# Sheet1.net
KiCad netlist of a schematic drawn in Altium Designer
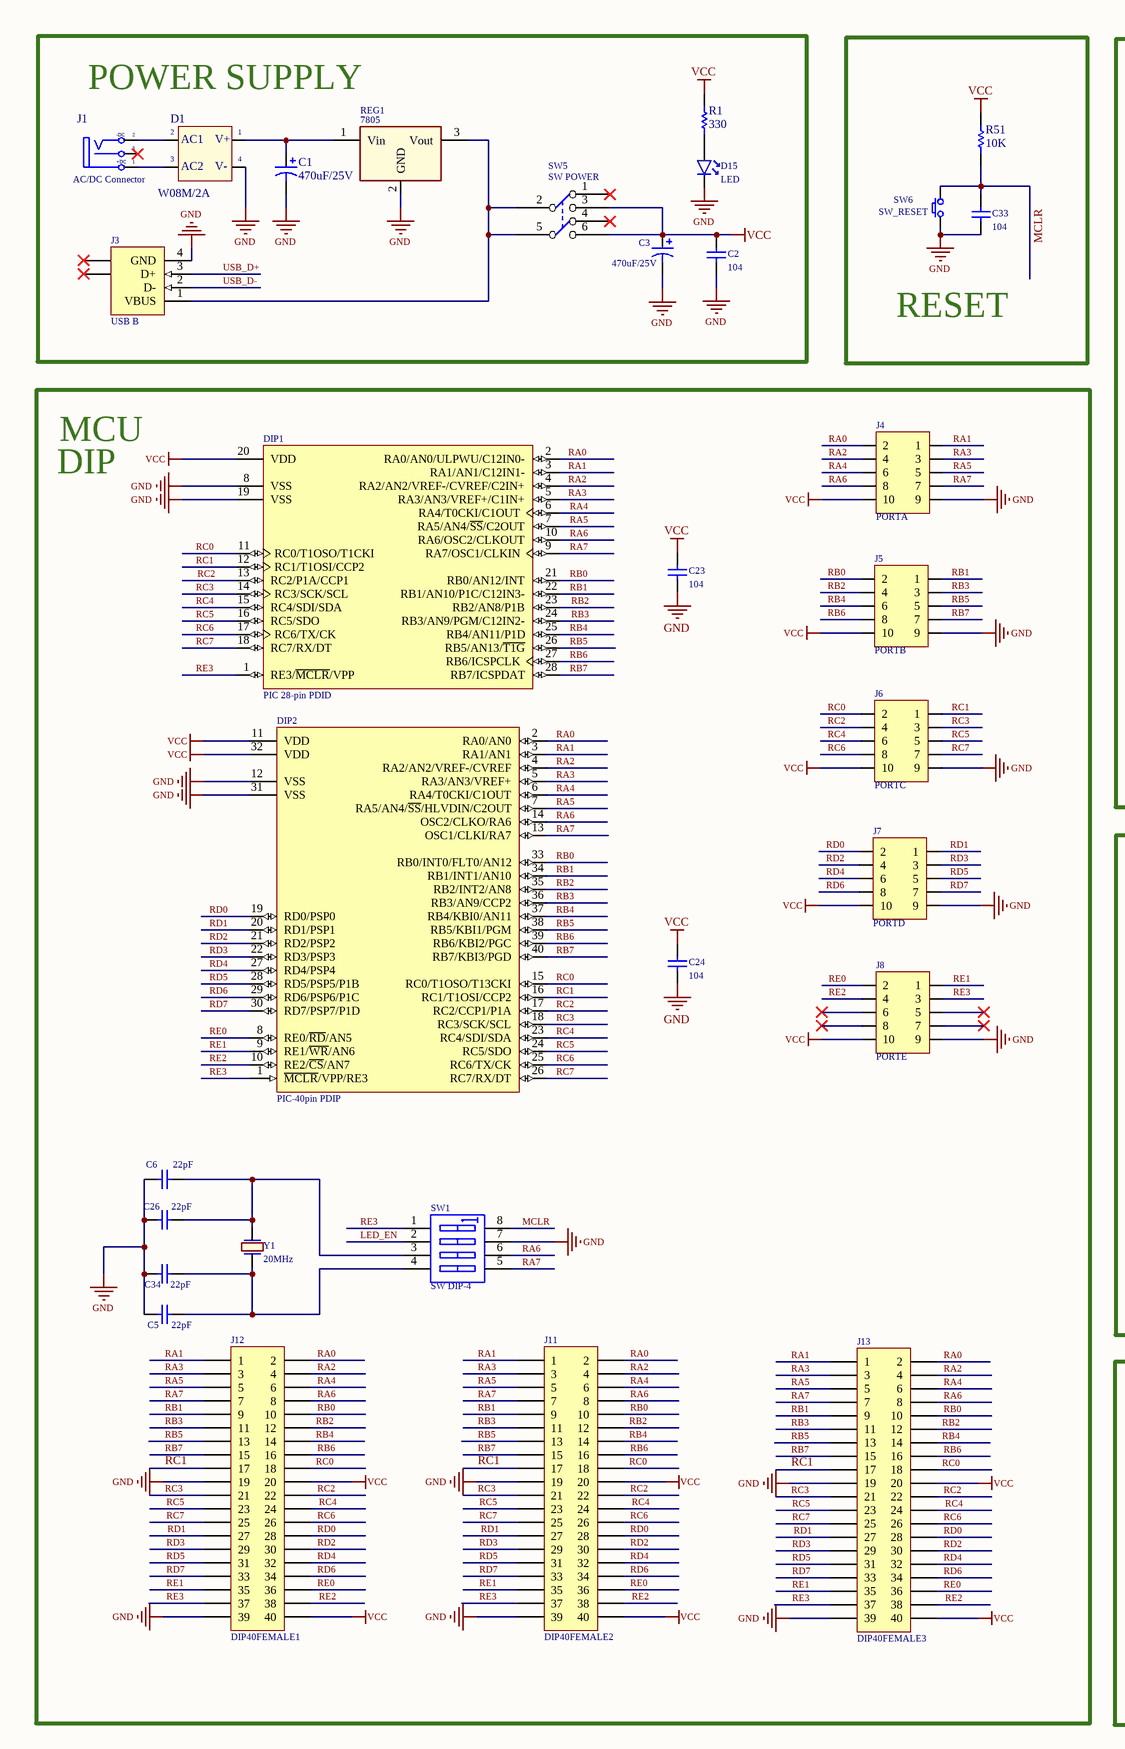
[diagram p0: Sheet1.SchDoc, left]
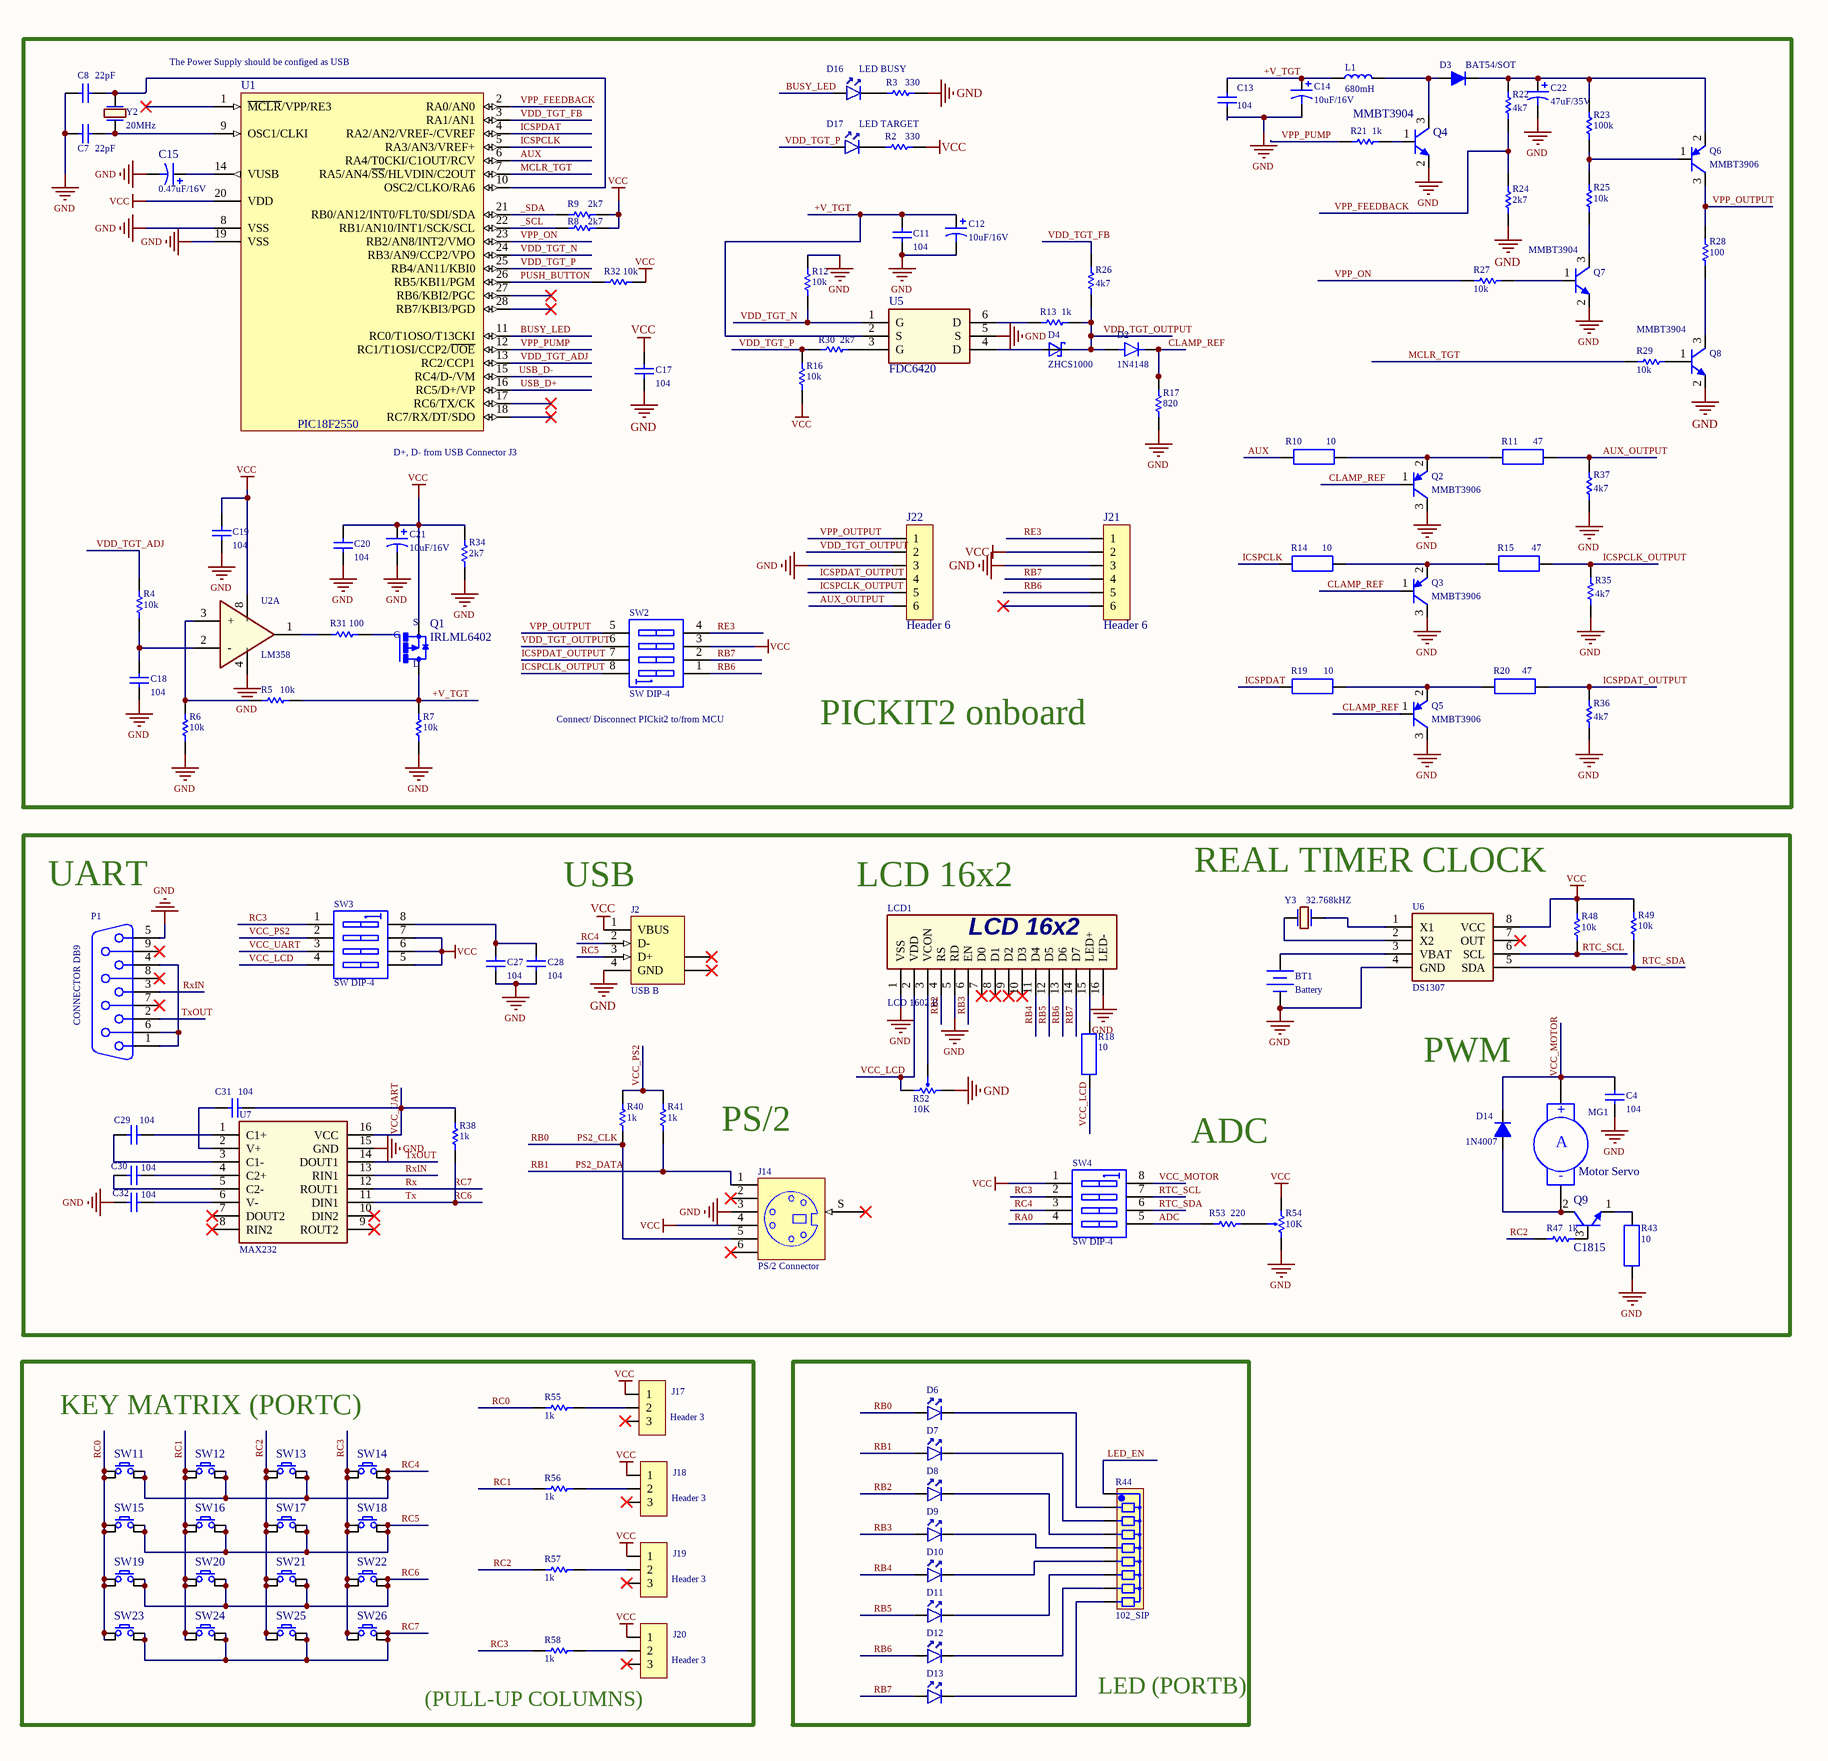
[diagram p1: Sheet1.SchDoc, right]

(export (version "E")
  (design (tool "Eeschema 10.0.6"))
  (components
    (comp (ref "BT1")
      (value "Battery")
      (footprint "CON CR2032")
      (libsource (lib "BKIT4U_LIB") (part "Battery"))
    )
    (comp (ref "C1")
      (value "470uF/25V")
      (footprint "CYL/D.300/LS.150/.031")
      (description "Polarized Capacitor (Axial)")
      (fields (field (name "PUBLISHER") "Altium Limited"))
      (libsource (lib "My Library") (part "Cap Pol 8mm"))
    )
    (comp (ref "C2")
      (value "104")
      (footprint "C 104")
      (description "Capacitor non-pol")
      (libsource (lib "BKIT4U_LIB") (part "Capacitor NP"))
    )
    (comp (ref "C3")
      (value "470uF/25V")
      (footprint "CYL/D.300/LS.150/.031")
      (description "Polarized Capacitor (Axial)")
      (fields (field (name "PUBLISHER") "Altium Limited"))
      (libsource (lib "My Library") (part "Cap Pol 8mm"))
    )
    (comp (ref "C4")
      (value "104")
      (footprint "C 0805 (2012)")
      (description "Capacitor non-pol")
      (libsource (lib "BKIT4U_LIB") (part "Capacitor NP"))
    )
    (comp (ref "C5")
      (value "22pF")
      (footprint "C 0805 (2012)")
      (description "Capacitor non-pol")
      (libsource (lib "BKIT4U_LIB") (part "Capacitor NP"))
    )
    (comp (ref "C6")
      (value "22pF")
      (footprint "C 0805 (2012)")
      (description "Capacitor non-pol")
      (libsource (lib "BKIT4U_LIB") (part "Capacitor NP"))
    )
    (comp (ref "C7")
      (value "22pF")
      (footprint "C 0805 (2012)")
      (description "Capacitor non-pol")
      (libsource (lib "BKIT4U_LIB") (part "Capacitor NP"))
    )
    (comp (ref "C8")
      (value "22pF")
      (footprint "C 0805 (2012)")
      (description "Capacitor non-pol")
      (libsource (lib "BKIT4U_LIB") (part "Capacitor NP"))
    )
    (comp (ref "C11")
      (value "104")
      (footprint "C 0805 (2012)")
      (description "Capacitor non-pol")
      (libsource (lib "BKIT4U_LIB") (part "Capacitor NP"))
    )
    (comp (ref "C12")
      (value "10uF/16V")
      (footprint "C5mm")
      (description "Polarized Capacitor (Axial)")
      (fields (field (name "PUBLISHER") "Altium Limited"))
      (libsource (lib "My Library") (part "Cap Pol 5mm"))
    )
    (comp (ref "C13")
      (value "104")
      (footprint "C 0805 (2012)")
      (description "Capacitor non-pol")
      (libsource (lib "BKIT4U_LIB") (part "Capacitor NP"))
    )
    (comp (ref "C14")
      (value "10uF/16V")
      (footprint "C5mm")
      (description "Polarized Capacitor (Axial)")
      (fields (field (name "PUBLISHER") "Altium Limited"))
      (libsource (lib "My Library") (part "Cap Pol 5mm"))
    )
    (comp (ref "C15")
      (value "0.47uF/16V")
      (footprint "C5mm")
      (description "Polarized Capacitor (Axial)")
      (fields (field (name "PUBLISHER") "Altium Limited"))
      (libsource (lib "My Library") (part "Cap Pol 5mm"))
    )
    (comp (ref "C17")
      (value "104")
      (footprint "C 0805 (2012)")
      (description "Capacitor non-pol")
      (libsource (lib "BKIT4U_LIB") (part "Capacitor NP"))
    )
    (comp (ref "C18")
      (value "104")
      (footprint "C 0805 (2012)")
      (description "Capacitor non-pol")
      (libsource (lib "BKIT4U_LIB") (part "Capacitor NP"))
    )
    (comp (ref "C19")
      (value "104")
      (footprint "C 0805 (2012)")
      (description "Capacitor non-pol")
      (libsource (lib "BKIT4U_LIB") (part "Capacitor NP"))
    )
    (comp (ref "C20")
      (value "104")
      (footprint "C 0805 (2012)")
      (description "Capacitor non-pol")
      (libsource (lib "BKIT4U_LIB") (part "Capacitor NP"))
    )
    (comp (ref "C21")
      (value "10uF/16V")
      (footprint "C5mm")
      (description "Polarized Capacitor (Axial)")
      (fields (field (name "PUBLISHER") "Altium Limited"))
      (libsource (lib "My Library") (part "Cap Pol 5mm"))
    )
    (comp (ref "C22")
      (value "47uF/35V")
      (footprint "C5mm")
      (description "Polarized Capacitor (Axial)")
      (fields (field (name "PUBLISHER") "Altium Limited"))
      (libsource (lib "My Library") (part "Cap Pol 5mm"))
    )
    (comp (ref "C23")
      (value "104")
      (footprint "C 0805 (2012)")
      (description "Capacitor non-pol")
      (libsource (lib "BKIT4U_LIB") (part "Capacitor NP"))
    )
    (comp (ref "C24")
      (value "104")
      (footprint "C 0805 (2012)")
      (description "Capacitor non-pol")
      (libsource (lib "BKIT4U_LIB") (part "Capacitor NP"))
    )
    (comp (ref "C26")
      (value "22pF")
      (footprint "C 0805 (2012)")
      (description "Capacitor non-pol")
      (libsource (lib "BKIT4U_LIB") (part "Capacitor NP"))
    )
    (comp (ref "C27")
      (value "104")
      (footprint "C 0805 (2012)")
      (description "Capacitor non-pol")
      (libsource (lib "BKIT4U_LIB") (part "Capacitor NP"))
    )
    (comp (ref "C28")
      (value "104")
      (footprint "C 0805 (2012)")
      (description "Capacitor non-pol")
      (libsource (lib "BKIT4U_LIB") (part "Capacitor NP"))
    )
    (comp (ref "C29")
      (value "104")
      (footprint "C 0805 (2012)")
      (description "Capacitor non-pol")
      (libsource (lib "BKIT4U_LIB") (part "Capacitor NP"))
    )
    (comp (ref "C30")
      (value "104")
      (footprint "C 0805 (2012)")
      (description "Capacitor non-pol")
      (libsource (lib "BKIT4U_LIB") (part "Capacitor NP"))
    )
    (comp (ref "C31")
      (value "104")
      (footprint "C 0805 (2012)")
      (description "Capacitor non-pol")
      (libsource (lib "BKIT4U_LIB") (part "Capacitor NP"))
    )
    (comp (ref "C32")
      (value "104")
      (footprint "C 0805 (2012)")
      (description "Capacitor non-pol")
      (libsource (lib "BKIT4U_LIB") (part "Capacitor NP"))
    )
    (comp (ref "C33")
      (value "104")
      (footprint "C 0805 (2012)")
      (description "Capacitor non-pol")
      (libsource (lib "BKIT4U_LIB") (part "Capacitor NP"))
    )
    (comp (ref "C34")
      (value "22pF")
      (footprint "C 0805 (2012)")
      (description "Capacitor non-pol")
      (libsource (lib "BKIT4U_LIB") (part "Capacitor NP"))
    )
    (comp (ref "D1")
      (value "W08M/2A")
      (footprint "BRIDGE DIODE 2A")
      (description "Convert AC to DC voltage, 4 pin")
      (libsource (lib "BKIT4U_LIB") (part "Diode Bridge"))
    )
    (comp (ref "D2")
      (value "1N4148")
      (footprint "SOT-23")
      (description "DIODE FAST SIGNAL 500MA/100V")
      (fields (field (name "MF") "MICROSS/On Semiconductor"))
      (libsource (lib "1N4148") (part "1N4148"))
    )
    (comp (ref "D3")
      (value "BAT54/SOT")
      (footprint "SOT-23")
      (description "Default Diode")
      (fields (field (name "PUBLISHER") "Altium Limited"))
      (libsource (lib "BKIT4U_LIB") (part "Diode"))
    )
    (comp (ref "D4")
      (value "ZHCS1000")
      (footprint "SOT-23")
      (description "Diode Schottky 40V 1A _DC_ Surface Mount SOT-23-3")
      (fields (field (name "MF") "Diodes Inc."))
      (libsource (lib "ZHCS1000") (part "ZHCS1000"))
    )
    (comp (ref "D6")
      (value "IR LED")
      (footprint "LED 3MM")
      (description "IR Led")
      (fields (field (name "PUBLISHER") "Altium Limited"))
      (libsource (lib "BKIT4U_LIB") (part "IR Led"))
    )
    (comp (ref "D7")
      (value "IR LED")
      (footprint "LED 3MM")
      (description "IR Led")
      (fields (field (name "PUBLISHER") "Altium Limited"))
      (libsource (lib "BKIT4U_LIB") (part "IR Led"))
    )
    (comp (ref "D8")
      (value "IR LED")
      (footprint "LED 3MM")
      (description "IR Led")
      (fields (field (name "PUBLISHER") "Altium Limited"))
      (libsource (lib "BKIT4U_LIB") (part "IR Led"))
    )
    (comp (ref "D9")
      (value "IR LED")
      (footprint "LED 3MM")
      (description "IR Led")
      (fields (field (name "PUBLISHER") "Altium Limited"))
      (libsource (lib "BKIT4U_LIB") (part "IR Led"))
    )
    (comp (ref "D10")
      (value "IR LED")
      (footprint "LED 3MM")
      (description "IR Led")
      (fields (field (name "PUBLISHER") "Altium Limited"))
      (libsource (lib "BKIT4U_LIB") (part "IR Led"))
    )
    (comp (ref "D11")
      (value "IR LED")
      (footprint "LED 3MM")
      (description "IR Led")
      (fields (field (name "PUBLISHER") "Altium Limited"))
      (libsource (lib "BKIT4U_LIB") (part "IR Led"))
    )
    (comp (ref "D12")
      (value "IR LED")
      (footprint "LED 3MM")
      (description "IR Led")
      (fields (field (name "PUBLISHER") "Altium Limited"))
      (libsource (lib "BKIT4U_LIB") (part "IR Led"))
    )
    (comp (ref "D13")
      (value "IR LED")
      (footprint "LED 3MM")
      (description "IR Led")
      (fields (field (name "PUBLISHER") "Altium Limited"))
      (libsource (lib "BKIT4U_LIB") (part "IR Led"))
    )
    (comp (ref "D14")
      (value "1N4007")
      (footprint "D1A")
      (description "Diode 1A")
      (libsource (lib "My Library") (part "D1A"))
    )
    (comp (ref "D15")
      (value "LED")
      (footprint "LED 3MM")
      (description "IR Led")
      (fields (field (name "PUBLISHER") "Altium Limited"))
      (libsource (lib "BKIT4U_LIB") (part "IR Led"))
    )
    (comp (ref "D16")
      (value "LED BUSY")
      (footprint "LED 3MM")
      (description "IR Led")
      (fields (field (name "PUBLISHER") "Altium Limited"))
      (libsource (lib "BKIT4U_LIB") (part "IR Led"))
    )
    (comp (ref "D17")
      (value "LED TARGET")
      (footprint "LED 3MM")
      (description "IR Led")
      (fields (field (name "PUBLISHER") "Altium Limited"))
      (libsource (lib "BKIT4U_LIB") (part "IR Led"))
    )
    (comp (ref "DIP1")
      (value "PIC 28-pin PDID")
      (footprint "SPDIP300-SP28")
      (fields (field (name "PUBLISHER") "Altium Limited"))
      (libsource (lib "Microchip Microcontroller 8-Bit PIC16") (part "PIC16F886-I/SP"))
    )
    (comp (ref "DIP2")
      (value "PIC-40pin PDIP")
      (footprint "PDIP600-P40")
      (fields (field (name "PUBLISHER") "Altium Limited"))
      (libsource (lib "Microchip Microcontroller 8-Bit PIC18") (part "PIC18F4620-I/P"))
    )
    (comp (ref "J1")
      (value "AC/DC Connector")
      (footprint "CON PWR 5MM")
      (description "DC input connector")
      (libsource (lib "BKIT4U_LIB") (part "CON DC PWR"))
    )
    (comp (ref "J2")
      (value "USB B")
      (footprint "CON USB B")
      (description "USB type B, 4 pins")
      (libsource (lib "BKIT4U_LIB") (part "CON USB B"))
    )
    (comp (ref "J3")
      (value "USB B")
      (footprint "CON USB B")
      (description "USB type B, 4 pins")
      (libsource (lib "") (part "CON USB B_1"))
    )
    (comp (ref "J4")
      (value "PORTA")
      (footprint "Header 5x2")
      (description "Header, 5-Pin, Dual row")
      (fields (field (name "PUBLISHER") "Altium Limited"))
      (libsource (lib "BKIT4U_LIB") (part "Header 5X2"))
    )
    (comp (ref "J5")
      (value "PORTB")
      (footprint "Header 5x2")
      (description "Header, 5-Pin, Dual row")
      (fields (field (name "PUBLISHER") "Altium Limited"))
      (libsource (lib "BKIT4U_LIB") (part "Header 5X2"))
    )
    (comp (ref "J6")
      (value "PORTC")
      (footprint "Header 5x2")
      (description "Header, 5-Pin, Dual row")
      (fields (field (name "PUBLISHER") "Altium Limited"))
      (libsource (lib "BKIT4U_LIB") (part "Header 5X2"))
    )
    (comp (ref "J7")
      (value "PORTD")
      (footprint "Header 5x2")
      (description "Header, 5-Pin, Dual row")
      (fields (field (name "PUBLISHER") "Altium Limited"))
      (libsource (lib "BKIT4U_LIB") (part "Header 5X2"))
    )
    (comp (ref "J8")
      (value "PORTE")
      (footprint "Header 5x2")
      (description "Header, 5-Pin, Dual row")
      (fields (field (name "PUBLISHER") "Altium Limited"))
      (libsource (lib "BKIT4U_LIB") (part "Header 5X2"))
    )
    (comp (ref "J11")
      (value "DIP40FEMALE2")
      (footprint "HDR2X20")
      (description "Header, 20-Pin, Dual row")
      (fields (field (name "PUBLISHER") "Altium Limited"))
      (libsource (lib "My library altium") (part "Header 20X2"))
    )
    (comp (ref "J12")
      (value "DIP40FEMALE1")
      (footprint "HDR2X20")
      (description "Header, 20-Pin, Dual row")
      (fields (field (name "PUBLISHER") "Altium Limited"))
      (libsource (lib "My library altium") (part "Header 20X2"))
    )
    (comp (ref "J13")
      (value "DIP40FEMALE3")
      (footprint "HDR2X20")
      (description "Header, 20-Pin, Dual row")
      (fields (field (name "PUBLISHER") "Altium Limited"))
      (libsource (lib "My library altium") (part "Header 20X2"))
    )
    (comp (ref "J14")
      (value "PS/2 Connector")
      (footprint "PS2-6PIN")
      (description "6 Pin Through Hole PS2 Socket (Kycon P/N)")
      (fields (field (name "PUBLISHER") "Altium Limited"))
      (libsource (lib "Miscellaneous Connectors") (part "PS2-6PIN"))
    )
    (comp (ref "J17")
      (value "Header 3")
      (footprint "Header 3")
      (description "Header, 3-Pin")
      (libsource (lib "BKIT4U_LIB") (part "Header 3"))
    )
    (comp (ref "J18")
      (value "Header 3")
      (footprint "Header 3")
      (description "Header, 3-Pin")
      (libsource (lib "BKIT4U_LIB") (part "Header 3"))
    )
    (comp (ref "J19")
      (value "Header 3")
      (footprint "Header 3")
      (description "Header, 3-Pin")
      (libsource (lib "BKIT4U_LIB") (part "Header 3"))
    )
    (comp (ref "J20")
      (value "Header 3")
      (footprint "Header 3")
      (description "Header, 3-Pin")
      (libsource (lib "BKIT4U_LIB") (part "Header 3"))
    )
    (comp (ref "J21")
      (value "Header 6")
      (footprint "Header 6")
      (description "Header, 6-Pin")
      (libsource (lib "BKIT4U_LIB") (part "Header 6"))
    )
    (comp (ref "J22")
      (value "Header 6")
      (footprint "Header 6")
      (description "Header, 6-Pin")
      (libsource (lib "BKIT4U_LIB") (part "Header 6"))
    )
    (comp (ref "L1")
      (value "680mH")
      (footprint "R 1/2W")
      (description "Inductor")
      (libsource (lib "BKIT4U_LIB") (part "Inductor"))
    )
    (comp (ref "LCD1")
      (value "LCD 1602 B")
      (footprint "LCD 16x2")
      (description "Character LCD 16x2")
      (libsource (lib "BKIT4U_LIB") (part "LCD 16x2"))
    )
    (comp (ref "MG1")
      (value "Motor Servo")
      (footprint "R 1206 (3216)")
      (description "Servo Motor")
      (fields (field (name "PUBLISHER") "Altium Limited"))
      (libsource (lib "Miscellaneous Devices") (part "Motor Servo"))
    )
    (comp (ref "P1")
      (value "CONNECTOR DB9")
      (footprint "CON DB9 FEMALE ROTATY")
      (description "Connector D-Sub 9")
      (libsource (lib "BKIT4U_LIB") (part "CON DB-9"))
    )
    (comp (ref "Q1")
      (value "IRLML6402")
      (footprint "SOT23")
      (description "P-Channel 20V 3.7A _Ta_ 1.3W _Ta_ Surface Mount Micro3â„¢/SOT-23")
      (fields (field (name "MF") "Infineon Technologies"))
      (libsource (lib "IRLML6402") (part "IRLML6402"))
    )
    (comp (ref "Q2")
      (value "MMBT3906")
      (footprint "SOT-23")
      (description "PNP Bipolar Transistor")
      (fields (field (name "PUBLISHER") "Altium Limited"))
      (libsource (lib "BKIT4U_LIB") (part "Transistor PNP"))
    )
    (comp (ref "Q3")
      (value "MMBT3906")
      (footprint "SOT-23")
      (description "PNP Bipolar Transistor")
      (fields (field (name "PUBLISHER") "Altium Limited"))
      (libsource (lib "BKIT4U_LIB") (part "Transistor PNP"))
    )
    (comp (ref "Q4")
      (value "MMBT3904")
      (footprint "SOT-23")
      (description "NPN Bipolar Transistor")
      (libsource (lib "BKIT4U_LIB") (part "Transistor NPN"))
    )
    (comp (ref "Q5")
      (value "MMBT3906")
      (footprint "SOT-23")
      (description "PNP Bipolar Transistor")
      (fields (field (name "PUBLISHER") "Altium Limited"))
      (libsource (lib "BKIT4U_LIB") (part "Transistor PNP"))
    )
    (comp (ref "Q6")
      (value "MMBT3906")
      (footprint "SOT-23")
      (description "PNP Bipolar Transistor")
      (fields (field (name "PUBLISHER") "Altium Limited"))
      (libsource (lib "BKIT4U_LIB") (part "Transistor PNP"))
    )
    (comp (ref "Q7")
      (value "MMBT3904")
      (footprint "SOT-23")
      (description "NPN Bipolar Transistor")
      (libsource (lib "BKIT4U_LIB") (part "Transistor NPN"))
    )
    (comp (ref "Q8")
      (value "MMBT3904")
      (footprint "SOT-23")
      (description "NPN Bipolar Transistor")
      (libsource (lib "BKIT4U_LIB") (part "Transistor NPN"))
    )
    (comp (ref "Q9")
      (value "C1815")
      (footprint "TO-126")
      (description "NPN Bipolar Transistor")
      (libsource (lib "BKIT4U_LIB") (part "Transistor NPN - C1815"))
    )
    (comp (ref "R1")
      (value "330")
      (footprint "R 1/4W")
      (description "Resistor")
      (fields (field (name "PUBLISHER") "Altium Limited"))
      (libsource (lib "BKIT4U_LIB") (part "Resistor"))
    )
    (comp (ref "R2")
      (value "330")
      (footprint "R 1/4W")
      (description "Resistor")
      (fields (field (name "PUBLISHER") "Altium Limited"))
      (libsource (lib "BKIT4U_LIB") (part "Resistor"))
    )
    (comp (ref "R3")
      (value "330")
      (footprint "R 1/4W")
      (description "Resistor")
      (fields (field (name "PUBLISHER") "Altium Limited"))
      (libsource (lib "BKIT4U_LIB") (part "Resistor"))
    )
    (comp (ref "R4")
      (value "10k")
      (footprint "R 1/4W")
      (description "Resistor")
      (fields (field (name "PUBLISHER") "Altium Limited"))
      (libsource (lib "BKIT4U_LIB") (part "Resistor"))
    )
    (comp (ref "R5")
      (value "10k")
      (footprint "R 1/4W")
      (description "Resistor")
      (fields (field (name "PUBLISHER") "Altium Limited"))
      (libsource (lib "BKIT4U_LIB") (part "Resistor"))
    )
    (comp (ref "R6")
      (value "10k")
      (footprint "R 1/4W")
      (description "Resistor")
      (fields (field (name "PUBLISHER") "Altium Limited"))
      (libsource (lib "BKIT4U_LIB") (part "Resistor"))
    )
    (comp (ref "R7")
      (value "10k")
      (footprint "R 1/4W")
      (description "Resistor")
      (fields (field (name "PUBLISHER") "Altium Limited"))
      (libsource (lib "BKIT4U_LIB") (part "Resistor"))
    )
    (comp (ref "R8")
      (value "2k7")
      (footprint "R 1/4W")
      (description "Resistor")
      (fields (field (name "PUBLISHER") "Altium Limited"))
      (libsource (lib "BKIT4U_LIB") (part "Resistor"))
    )
    (comp (ref "R9")
      (value "2k7")
      (footprint "R 1/4W")
      (description "Resistor")
      (fields (field (name "PUBLISHER") "Altium Limited"))
      (libsource (lib "BKIT4U_LIB") (part "Resistor"))
    )
    (comp (ref "R10")
      (value "10")
      (footprint "R 1/4W")
      (description "Resistor 1W")
      (libsource (lib "My Library") (part "R1W"))
    )
    (comp (ref "R11")
      (value "47")
      (footprint "R 1/4W")
      (description "Resistor 1W")
      (libsource (lib "My Library") (part "R1W"))
    )
    (comp (ref "R12")
      (value "10k")
      (footprint "R 1/4W")
      (description "Resistor")
      (fields (field (name "PUBLISHER") "Altium Limited"))
      (libsource (lib "BKIT4U_LIB") (part "Resistor"))
    )
    (comp (ref "R13")
      (value "1k")
      (footprint "R 1/4W")
      (description "Resistor")
      (fields (field (name "PUBLISHER") "Altium Limited"))
      (libsource (lib "BKIT4U_LIB") (part "Resistor"))
    )
    (comp (ref "R14")
      (value "10")
      (footprint "R 1/4W")
      (description "Resistor 1W")
      (libsource (lib "My Library") (part "R1W"))
    )
    (comp (ref "R15")
      (value "47")
      (footprint "R 1/4W")
      (description "Resistor 1W")
      (libsource (lib "My Library") (part "R1W"))
    )
    (comp (ref "R16")
      (value "10k")
      (footprint "R 1/4W")
      (description "Resistor")
      (fields (field (name "PUBLISHER") "Altium Limited"))
      (libsource (lib "BKIT4U_LIB") (part "Resistor"))
    )
    (comp (ref "R17")
      (value "820")
      (footprint "R 1/4W")
      (description "Resistor")
      (fields (field (name "PUBLISHER") "Altium Limited"))
      (libsource (lib "BKIT4U_LIB") (part "Resistor"))
    )
    (comp (ref "R18")
      (value "10")
      (footprint "R 1/4W")
      (description "Resistor 1W")
      (libsource (lib "My Library") (part "R1W"))
    )
    (comp (ref "R19")
      (value "10")
      (footprint "R 1/4W")
      (description "Resistor 1W")
      (libsource (lib "My Library") (part "R1W"))
    )
    (comp (ref "R20")
      (value "47")
      (footprint "R 1/4W")
      (description "Resistor 1W")
      (libsource (lib "My Library") (part "R1W"))
    )
    (comp (ref "R21")
      (value "1k")
      (footprint "R 1/4W")
      (description "Resistor")
      (fields (field (name "PUBLISHER") "Altium Limited"))
      (libsource (lib "BKIT4U_LIB") (part "Resistor"))
    )
    (comp (ref "R22")
      (value "4k7")
      (footprint "R 1/4W")
      (description "Resistor")
      (fields (field (name "PUBLISHER") "Altium Limited"))
      (libsource (lib "BKIT4U_LIB") (part "Resistor"))
    )
    (comp (ref "R23")
      (value "100k")
      (footprint "R 1/4W")
      (description "Resistor")
      (fields (field (name "PUBLISHER") "Altium Limited"))
      (libsource (lib "BKIT4U_LIB") (part "Resistor"))
    )
    (comp (ref "R24")
      (value "2k7")
      (footprint "R 1/4W")
      (description "Resistor")
      (fields (field (name "PUBLISHER") "Altium Limited"))
      (libsource (lib "BKIT4U_LIB") (part "Resistor"))
    )
    (comp (ref "R25")
      (value "10k")
      (footprint "R 1/4W")
      (description "Resistor")
      (fields (field (name "PUBLISHER") "Altium Limited"))
      (libsource (lib "BKIT4U_LIB") (part "Resistor"))
    )
    (comp (ref "R26")
      (value "4k7")
      (footprint "R 1/4W")
      (description "Resistor")
      (fields (field (name "PUBLISHER") "Altium Limited"))
      (libsource (lib "BKIT4U_LIB") (part "Resistor"))
    )
    (comp (ref "R27")
      (value "10k")
      (footprint "R 1/4W")
      (description "Resistor")
      (fields (field (name "PUBLISHER") "Altium Limited"))
      (libsource (lib "BKIT4U_LIB") (part "Resistor"))
    )
    (comp (ref "R28")
      (value "100")
      (footprint "R 1/4W")
      (description "Resistor")
      (fields (field (name "PUBLISHER") "Altium Limited"))
      (libsource (lib "BKIT4U_LIB") (part "Resistor"))
    )
    (comp (ref "R29")
      (value "10k")
      (footprint "R 1/4W")
      (description "Resistor")
      (fields (field (name "PUBLISHER") "Altium Limited"))
      (libsource (lib "BKIT4U_LIB") (part "Resistor"))
    )
    (comp (ref "R30")
      (value "2k7")
      (footprint "R 1/4W")
      (description "Resistor")
      (fields (field (name "PUBLISHER") "Altium Limited"))
      (libsource (lib "BKIT4U_LIB") (part "Resistor"))
    )
    (comp (ref "R31")
      (value "100")
      (footprint "R 1/4W")
      (description "Resistor")
      (fields (field (name "PUBLISHER") "Altium Limited"))
      (libsource (lib "BKIT4U_LIB") (part "Resistor"))
    )
    (comp (ref "R32")
      (value "10k")
      (footprint "R 1/4W")
      (description "Resistor")
      (fields (field (name "PUBLISHER") "Altium Limited"))
      (libsource (lib "BKIT4U_LIB") (part "Resistor"))
    )
    (comp (ref "R34")
      (value "2k7")
      (footprint "R 1/4W")
      (description "Resistor")
      (fields (field (name "PUBLISHER") "Altium Limited"))
      (libsource (lib "BKIT4U_LIB") (part "Resistor"))
    )
    (comp (ref "R35")
      (value "4k7")
      (footprint "R 1/4W")
      (description "Resistor")
      (fields (field (name "PUBLISHER") "Altium Limited"))
      (libsource (lib "BKIT4U_LIB") (part "Resistor"))
    )
    (comp (ref "R36")
      (value "4k7")
      (footprint "R 1/4W")
      (description "Resistor")
      (fields (field (name "PUBLISHER") "Altium Limited"))
      (libsource (lib "BKIT4U_LIB") (part "Resistor"))
    )
    (comp (ref "R37")
      (value "4k7")
      (footprint "R 1/4W")
      (description "Resistor")
      (fields (field (name "PUBLISHER") "Altium Limited"))
      (libsource (lib "BKIT4U_LIB") (part "Resistor"))
    )
    (comp (ref "R38")
      (value "1k")
      (footprint "R 1/4W")
      (description "Resistor")
      (fields (field (name "PUBLISHER") "Altium Limited"))
      (libsource (lib "BKIT4U_LIB") (part "Resistor"))
    )
    (comp (ref "R40")
      (value "1k")
      (footprint "R 1/4W")
      (description "Resistor")
      (fields (field (name "PUBLISHER") "Altium Limited"))
      (libsource (lib "BKIT4U_LIB") (part "Resistor"))
    )
    (comp (ref "R41")
      (value "1k")
      (footprint "R 1/4W")
      (description "Resistor")
      (fields (field (name "PUBLISHER") "Altium Limited"))
      (libsource (lib "BKIT4U_LIB") (part "Resistor"))
    )
    (comp (ref "R43")
      (value "10")
      (footprint "R 1/4W")
      (description "Resistor 1W")
      (libsource (lib "My Library") (part "R1W"))
    )
    (comp (ref "R44")
      (value "102_SIP")
      (footprint "RN8")
      (description "Resistor 8 (Thanh)")
      (libsource (lib "My Library") (part "RN8"))
    )
    (comp (ref "R47")
      (value "1k")
      (footprint "R 1/4W")
      (description "Resistor")
      (fields (field (name "PUBLISHER") "Altium Limited"))
      (libsource (lib "BKIT4U_LIB") (part "Resistor"))
    )
    (comp (ref "R48")
      (value "10k")
      (footprint "R 1/4W")
      (description "Resistor")
      (fields (field (name "PUBLISHER") "Altium Limited"))
      (libsource (lib "BKIT4U_LIB") (part "Resistor"))
    )
    (comp (ref "R49")
      (value "10k")
      (footprint "R 1/4W")
      (description "Resistor")
      (fields (field (name "PUBLISHER") "Altium Limited"))
      (libsource (lib "BKIT4U_LIB") (part "Resistor"))
    )
    (comp (ref "R51")
      (value "10K")
      (footprint "R 1/4W")
      (description "Resistor")
      (fields (field (name "PUBLISHER") "Altium Limited"))
      (libsource (lib "BKIT4U_LIB") (part "Resistor"))
    )
    (comp (ref "R52")
      (value "10K")
      (footprint "R VAR D")
      (description "Resistor Variable")
      (libsource (lib "BKIT4U_LIB") (part "Resistor Variable"))
    )
    (comp (ref "R53")
      (value "220")
      (footprint "R 1/4W")
      (description "Resistor")
      (fields (field (name "PUBLISHER") "Altium Limited"))
      (libsource (lib "BKIT4U_LIB") (part "Resistor"))
    )
    (comp (ref "R54")
      (value "10K")
      (footprint "R VAR B")
      (description "Resistor Variable")
      (libsource (lib "BKIT4U_LIB") (part "Resistor Variable"))
    )
    (comp (ref "R55")
      (value "1k")
      (footprint "R 1/4W")
      (description "Resistor")
      (fields (field (name "PUBLISHER") "Altium Limited"))
      (libsource (lib "BKIT4U_LIB") (part "Resistor"))
    )
    (comp (ref "R56")
      (value "1k")
      (footprint "R 1/4W")
      (description "Resistor")
      (fields (field (name "PUBLISHER") "Altium Limited"))
      (libsource (lib "BKIT4U_LIB") (part "Resistor"))
    )
    (comp (ref "R57")
      (value "1k")
      (footprint "R 1/4W")
      (description "Resistor")
      (fields (field (name "PUBLISHER") "Altium Limited"))
      (libsource (lib "BKIT4U_LIB") (part "Resistor"))
    )
    (comp (ref "R58")
      (value "1k")
      (footprint "R 1/4W")
      (description "Resistor")
      (fields (field (name "PUBLISHER") "Altium Limited"))
      (libsource (lib "BKIT4U_LIB") (part "Resistor"))
    )
    (comp (ref "REG1")
      (value "7805")
      (footprint "TO-220/HeatSink")
      (description "LDO Fixed Voltage regulator")
      (libsource (lib "BKIT4U_LIB") (part "78xx/78Mxx"))
    )
    (comp (ref "SW1")
      (value "SW DIP-4")
      (footprint "SW/DIP4")
      (description "WS-DITV 2.54 mm small compact THT flat actuator with top tape")
      (fields
        (field (name "MANUFACTURER") "Wurth Elektronik")
        (field (name "PART NO.") "418127160904")
        (field (name "CREATED BY") "Baojun Chen")
      )
      (libsource (lib "") (part "SWDIP4_1"))
    )
    (comp (ref "SW2")
      (value "SW DIP-4")
      (footprint "SW/DIP4")
      (description "WS-DITV 2.54 mm small compact THT flat actuator with top tape")
      (fields
        (field (name "MANUFACTURER") "Wurth Elektronik")
        (field (name "PART NO.") "418127160904")
        (field (name "CREATED BY") "Baojun Chen")
      )
      (libsource (lib "My Library") (part "SWDIP4"))
    )
    (comp (ref "SW3")
      (value "SW DIP-4")
      (footprint "SW/DIP4")
      (description "WS-DITV 2.54 mm small compact THT flat actuator with top tape")
      (fields
        (field (name "MANUFACTURER") "Wurth Elektronik")
        (field (name "PART NO.") "418127160904")
        (field (name "CREATED BY") "Baojun Chen")
      )
      (libsource (lib "") (part "SWDIP4_1"))
    )
    (comp (ref "SW4")
      (value "SW DIP-4")
      (footprint "SW/DIP4")
      (description "WS-DITV 2.54 mm small compact THT flat actuator with top tape")
      (fields
        (field (name "MANUFACTURER") "Wurth Elektronik")
        (field (name "PART NO.") "418127160904")
        (field (name "CREATED BY") "Baojun Chen")
      )
      (libsource (lib "") (part "SWDIP4_1"))
    )
    (comp (ref "SW5")
      (value "SW POWER")
      (footprint "SW/6/DPDT/PUSH")
      (libsource (lib "BKIT4U_LIB") (part "SW DPDT/2S"))
    )
    (comp (ref "SW6")
      (value "SW_RESET")
      (footprint "SW/2/DIP")
      (description "Tact switch 2 pin")
      (libsource (lib "BKIT4U_LIB") (part "SW SPST"))
    )
    (comp (ref "SW11")
      (value "Tact Switch")
      (footprint "SW/4/SMD/SMALL")
      (description "Tact switch 4 pin")
      (libsource (lib "BKIT4U_LIB") (part "SW SPST-4"))
    )
    (comp (ref "SW12")
      (value "Tact Switch")
      (footprint "SW/4/SMD/SMALL")
      (description "Tact switch 4 pin")
      (libsource (lib "BKIT4U_LIB") (part "SW SPST-4"))
    )
    (comp (ref "SW13")
      (value "Tact Switch")
      (footprint "SW/4/SMD/SMALL")
      (description "Tact switch 4 pin")
      (libsource (lib "BKIT4U_LIB") (part "SW SPST-4"))
    )
    (comp (ref "SW14")
      (value "Tact Switch")
      (footprint "SW/4/SMD/SMALL")
      (description "Tact switch 4 pin")
      (libsource (lib "BKIT4U_LIB") (part "SW SPST-4"))
    )
    (comp (ref "SW15")
      (value "Tact Switch")
      (footprint "SW/4/SMD/SMALL")
      (description "Tact switch 4 pin")
      (libsource (lib "BKIT4U_LIB") (part "SW SPST-4"))
    )
    (comp (ref "SW16")
      (value "Tact Switch")
      (footprint "SW/4/SMD/SMALL")
      (description "Tact switch 4 pin")
      (libsource (lib "BKIT4U_LIB") (part "SW SPST-4"))
    )
    (comp (ref "SW17")
      (value "Tact Switch")
      (footprint "SW/4/SMD/SMALL")
      (description "Tact switch 4 pin")
      (libsource (lib "BKIT4U_LIB") (part "SW SPST-4"))
    )
    (comp (ref "SW18")
      (value "Tact Switch")
      (footprint "SW/4/SMD/SMALL")
      (description "Tact switch 4 pin")
      (libsource (lib "BKIT4U_LIB") (part "SW SPST-4"))
    )
    (comp (ref "SW19")
      (value "Tact Switch")
      (footprint "SW/4/SMD/SMALL")
      (description "Tact switch 4 pin")
      (libsource (lib "BKIT4U_LIB") (part "SW SPST-4"))
    )
    (comp (ref "SW20")
      (value "Tact Switch")
      (footprint "SW/4/SMD/SMALL")
      (description "Tact switch 4 pin")
      (libsource (lib "BKIT4U_LIB") (part "SW SPST-4"))
    )
    (comp (ref "SW21")
      (value "Tact Switch")
      (footprint "SW/4/SMD/SMALL")
      (description "Tact switch 4 pin")
      (libsource (lib "BKIT4U_LIB") (part "SW SPST-4"))
    )
    (comp (ref "SW22")
      (value "Tact Switch")
      (footprint "SW/4/SMD/SMALL")
      (description "Tact switch 4 pin")
      (libsource (lib "BKIT4U_LIB") (part "SW SPST-4"))
    )
    (comp (ref "SW23")
      (value "Tact Switch")
      (footprint "SW/4/SMD/SMALL")
      (description "Tact switch 4 pin")
      (libsource (lib "BKIT4U_LIB") (part "SW SPST-4"))
    )
    (comp (ref "SW24")
      (value "Tact Switch")
      (footprint "SW/4/SMD/SMALL")
      (description "Tact switch 4 pin")
      (libsource (lib "BKIT4U_LIB") (part "SW SPST-4"))
    )
    (comp (ref "SW25")
      (value "Tact Switch")
      (footprint "SW/4/SMD/SMALL")
      (description "Tact switch 4 pin")
      (libsource (lib "BKIT4U_LIB") (part "SW SPST-4"))
    )
    (comp (ref "SW26")
      (value "Tact Switch")
      (footprint "SW/4/SMD/SMALL")
      (description "Tact switch 4 pin")
      (libsource (lib "BKIT4U_LIB") (part "SW SPST-4"))
    )
    (comp (ref "U1")
      (value "PIC18F2550")
      (footprint "SPDIP300-SP28")
      (fields (field (name "PUBLISHER") "Altium Limited"))
      (libsource (lib "Microchip Microcontroller 8-Bit PIC18") (part "PIC18F2550-I/SP"))
    )
    (comp (ref "U2")
      (value "LM358")
      (footprint "SOIC-8")
      (description "Low Power Dual Operational Amplifiers")
      (libsource (lib "BKIT4U_LIB") (part "LM358"))
    )
    (comp (ref "U5")
      (value "FDC6420")
      (footprint "SOT-6")
      (description "20V N & P-Channel PowerTrenchÒ MOSFETs")
      (libsource (lib "BKIT4U_LIB") (part "FDC6420"))
    )
    (comp (ref "U6") (value "DS1307") (footprint "DIP 8") (libsource (lib "BKIT4U_LIB") (part "DS1307")))
    (comp (ref "U7")
      (value "MAX232")
      (footprint "SOIC-16")
      (description "RS-232 Line Driver/Receiver")
      (libsource (lib "BKIT4U_LIB") (part "MAX232"))
    )
    (comp (ref "Y1")
      (value "20MHz")
      (footprint "Crystal HC49S DIP")
      (libsource (lib "BKIT4U_LIB") (part "Crystal"))
    )
    (comp (ref "Y2")
      (value "20MHz")
      (footprint "Crystal HC49S DIP")
      (libsource (lib "BKIT4U_LIB") (part "Crystal"))
    )
    (comp (ref "Y3") (value "32.768kHZ") (footprint "Crystal DIP-2") (libsource (lib "") (part "Crystal_1")))
  )
  (nets
    (net (code "1") (name "/+V_TGT") (class "Default")
      (node (ref "C11") (pin "1") (pinfunction "1_1") (pintype "passive"))
      (node (ref "C12") (pin "1") (pinfunction "1_1") (pintype "passive"))
      (node (ref "C13") (pin "1") (pinfunction "1_1") (pintype "passive"))
      (node (ref "C14") (pin "1") (pinfunction "1_1") (pintype "passive"))
      (node (ref "L1") (pin "1") (pinfunction "1_1") (pintype "passive"))
      (node (ref "Q1") (pin "3") (pinfunction "D_3") (pintype "passive"))
      (node (ref "R5") (pin "2") (pinfunction "2_2") (pintype "passive"))
      (node (ref "R7") (pin "2") (pinfunction "2_2") (pintype "passive"))
      (node (ref "U5") (pin "2") (pinfunction "S_2") (pintype "passive"))
    )
    (net (code "2") (name "/ADC") (class "Default")
      (node (ref "R53") (pin "1") (pinfunction "1_1") (pintype "passive"))
      (node (ref "SW4") (pin "5") (pinfunction "5_5") (pintype "passive"))
    )
    (net (code "3") (name "/AUX") (class "Default")
      (node (ref "R10") (pin "1") (pinfunction "1_1") (pintype "passive"))
      (node (ref "U1") (pin "6") (pinfunction "RA4/T0CKI/C1OUT/RCV_6") (pintype "bidirectional"))
    )
    (net (code "4") (name "/AUX_OUTPUT") (class "Default")
      (node (ref "J22") (pin "6") (pinfunction "6_6") (pintype "passive"))
      (node (ref "R11") (pin "2") (pinfunction "2_2") (pintype "passive"))
      (node (ref "R37") (pin "2") (pinfunction "2_2") (pintype "passive"))
    )
    (net (code "5") (name "/BUSY_LED") (class "Default")
      (node (ref "D16") (pin "1") (pinfunction "A_1") (pintype "passive"))
      (node (ref "U1") (pin "11") (pinfunction "RC0/T1OSO/T13CKI_11") (pintype "bidirectional"))
    )
    (net (code "6") (name "/CLAMP_REF") (class "Default")
      (node (ref "D2") (pin "C") (pinfunction "C_C") (pintype "passive"))
      (node (ref "Q2") (pin "1") (pinfunction "B_1") (pintype "passive"))
      (node (ref "Q3") (pin "1") (pinfunction "B_1") (pintype "passive"))
      (node (ref "Q5") (pin "1") (pinfunction "B_1") (pintype "passive"))
      (node (ref "R17") (pin "2") (pinfunction "2_2") (pintype "passive"))
    )
    (net (code "7") (name "/ICSPCLK") (class "Default")
      (node (ref "R14") (pin "1") (pinfunction "1_1") (pintype "passive"))
      (node (ref "U1") (pin "5") (pinfunction "RA3/AN3/VREF+_5") (pintype "bidirectional"))
    )
    (net (code "8") (name "/ICSPCLK_OUTPUT") (class "Default")
      (node (ref "J22") (pin "5") (pinfunction "5_5") (pintype "passive"))
      (node (ref "R15") (pin "2") (pinfunction "2_2") (pintype "passive"))
      (node (ref "R35") (pin "2") (pinfunction "2_2") (pintype "passive"))
      (node (ref "SW2") (pin "8") (pinfunction "8_8") (pintype "passive"))
    )
    (net (code "9") (name "/ICSPDAT") (class "Default")
      (node (ref "R19") (pin "1") (pinfunction "1_1") (pintype "passive"))
      (node (ref "U1") (pin "4") (pinfunction "RA2/AN2/VREF-/CVREF_4") (pintype "bidirectional"))
    )
    (net (code "10") (name "/ICSPDAT_OUTPUT") (class "Default")
      (node (ref "J22") (pin "4") (pinfunction "4_4") (pintype "passive"))
      (node (ref "R20") (pin "2") (pinfunction "2_2") (pintype "passive"))
      (node (ref "R36") (pin "2") (pinfunction "2_2") (pintype "passive"))
      (node (ref "SW2") (pin "7") (pinfunction "7_7") (pintype "passive"))
    )
    (net (code "11") (name "/LED_EN") (class "Default")
      (node (ref "R44") (pin "1") (pinfunction "1_1") (pintype "passive"))
      (node (ref "SW1") (pin "2") (pinfunction "2_2") (pintype "passive"))
    )
    (net (code "12") (name "/MCLR") (class "Default")
      (node (ref "C33") (pin "1") (pinfunction "1_1") (pintype "passive"))
      (node (ref "R51") (pin "1") (pinfunction "1_1") (pintype "passive"))
      (node (ref "SW1") (pin "8") (pinfunction "8_8") (pintype "passive"))
      (node (ref "SW6") (pin "2") (pinfunction "2_2") (pintype "passive"))
    )
    (net (code "13") (name "/MCLR_TGT") (class "Default")
      (node (ref "R29") (pin "2") (pinfunction "2_2") (pintype "passive"))
      (node (ref "U1") (pin "7") (pinfunction "RA5/AN4/~{SS}/HLVDIN/C2OUT_7") (pintype "bidirectional"))
    )
    (net (code "14") (name "/PS2_CLK") (class "Default")
      (node (ref "D6") (pin "1") (pinfunction "A_1") (pintype "passive"))
      (node (ref "DIP1") (pin "21") (pinfunction "RB0/AN12/INT_21") (pintype "bidirectional"))
      (node (ref "DIP2") (pin "33") (pinfunction "RB0/INT0/FLT0/AN12_33") (pintype "bidirectional"))
      (node (ref "J11") (pin "10") (pinfunction "10_10") (pintype "passive"))
      (node (ref "J12") (pin "10") (pinfunction "10_10") (pintype "passive"))
      (node (ref "J13") (pin "10") (pinfunction "10_10") (pintype "passive"))
      (node (ref "J14") (pin "5") (pinfunction "5_5") (pintype "passive"))
      (node (ref "J5") (pin "2") (pinfunction "2_2") (pintype "passive"))
      (node (ref "R40") (pin "1") (pinfunction "1_1") (pintype "passive"))
    )
    (net (code "15") (name "/PS2_DATA") (class "Default")
      (node (ref "D7") (pin "1") (pinfunction "A_1") (pintype "passive"))
      (node (ref "DIP1") (pin "22") (pinfunction "RB1/AN10/P1C/C12IN3-_22") (pintype "bidirectional"))
      (node (ref "DIP2") (pin "34") (pinfunction "RB1/INT1/AN10_34") (pintype "bidirectional"))
      (node (ref "J11") (pin "9") (pinfunction "9_9") (pintype "passive"))
      (node (ref "J12") (pin "9") (pinfunction "9_9") (pintype "passive"))
      (node (ref "J13") (pin "9") (pinfunction "9_9") (pintype "passive"))
      (node (ref "J14") (pin "1") (pinfunction "1_1") (pintype "passive"))
      (node (ref "J5") (pin "1") (pinfunction "1_1") (pintype "passive"))
      (node (ref "R41") (pin "1") (pinfunction "1_1") (pintype "passive"))
    )
    (net (code "16") (name "/PUSH_BUTTON") (class "Default")
      (node (ref "R32") (pin "1") (pinfunction "1_1") (pintype "passive"))
      (node (ref "U1") (pin "26") (pinfunction "RB5/KBI1/PGM_26") (pintype "bidirectional"))
    )
    (net (code "17") (name "/RA0") (class "Default")
      (node (ref "DIP1") (pin "2") (pinfunction "RA0/AN0/ULPWU/C12IN0-_2") (pintype "bidirectional"))
      (node (ref "DIP2") (pin "2") (pinfunction "RA0/AN0_2") (pintype "bidirectional"))
      (node (ref "J11") (pin "2") (pinfunction "2_2") (pintype "passive"))
      (node (ref "J12") (pin "2") (pinfunction "2_2") (pintype "passive"))
      (node (ref "J13") (pin "2") (pinfunction "2_2") (pintype "passive"))
      (node (ref "J4") (pin "2") (pinfunction "2_2") (pintype "passive"))
      (node (ref "SW4") (pin "4") (pinfunction "4_4") (pintype "passive"))
    )
    (net (code "18") (name "/RA1") (class "Default")
      (node (ref "DIP1") (pin "3") (pinfunction "RA1/AN1/C12IN1-_3") (pintype "bidirectional"))
      (node (ref "DIP2") (pin "3") (pinfunction "RA1/AN1_3") (pintype "bidirectional"))
      (node (ref "J11") (pin "1") (pinfunction "1_1") (pintype "passive"))
      (node (ref "J12") (pin "1") (pinfunction "1_1") (pintype "passive"))
      (node (ref "J13") (pin "1") (pinfunction "1_1") (pintype "passive"))
      (node (ref "J4") (pin "1") (pinfunction "1_1") (pintype "passive"))
    )
    (net (code "19") (name "/RA2") (class "Default")
      (node (ref "DIP1") (pin "4") (pinfunction "RA2/AN2/VREF-/CVREF/C2IN+_4") (pintype "bidirectional"))
      (node (ref "DIP2") (pin "4") (pinfunction "RA2/AN2/VREF-/CVREF_4") (pintype "bidirectional"))
      (node (ref "J11") (pin "4") (pinfunction "4_4") (pintype "passive"))
      (node (ref "J12") (pin "4") (pinfunction "4_4") (pintype "passive"))
      (node (ref "J13") (pin "4") (pinfunction "4_4") (pintype "passive"))
      (node (ref "J4") (pin "4") (pinfunction "4_4") (pintype "passive"))
    )
    (net (code "20") (name "/RA3") (class "Default")
      (node (ref "DIP1") (pin "5") (pinfunction "RA3/AN3/VREF+/C1IN+_5") (pintype "bidirectional"))
      (node (ref "DIP2") (pin "5") (pinfunction "RA3/AN3/VREF+_5") (pintype "bidirectional"))
      (node (ref "J11") (pin "3") (pinfunction "3_3") (pintype "passive"))
      (node (ref "J12") (pin "3") (pinfunction "3_3") (pintype "passive"))
      (node (ref "J13") (pin "3") (pinfunction "3_3") (pintype "passive"))
      (node (ref "J4") (pin "3") (pinfunction "3_3") (pintype "passive"))
    )
    (net (code "21") (name "/RA4") (class "Default")
      (node (ref "DIP1") (pin "6") (pinfunction "RA4/T0CKI/C1OUT_6") (pintype "bidirectional"))
      (node (ref "DIP2") (pin "6") (pinfunction "RA4/T0CKI/C1OUT_6") (pintype "bidirectional"))
      (node (ref "J11") (pin "6") (pinfunction "6_6") (pintype "passive"))
      (node (ref "J12") (pin "6") (pinfunction "6_6") (pintype "passive"))
      (node (ref "J13") (pin "6") (pinfunction "6_6") (pintype "passive"))
      (node (ref "J4") (pin "6") (pinfunction "6_6") (pintype "passive"))
    )
    (net (code "22") (name "/RA5") (class "Default")
      (node (ref "DIP1") (pin "7") (pinfunction "RA5/AN4/~{SS}/C2OUT_7") (pintype "bidirectional"))
      (node (ref "DIP2") (pin "7") (pinfunction "RA5/AN4/~{SS}/HLVDIN/C2OUT_7") (pintype "bidirectional"))
      (node (ref "J11") (pin "5") (pinfunction "5_5") (pintype "passive"))
      (node (ref "J12") (pin "5") (pinfunction "5_5") (pintype "passive"))
      (node (ref "J13") (pin "5") (pinfunction "5_5") (pintype "passive"))
      (node (ref "J4") (pin "5") (pinfunction "5_5") (pintype "passive"))
    )
    (net (code "23") (name "/RA6") (class "Default")
      (node (ref "DIP1") (pin "10") (pinfunction "RA6/OSC2/CLKOUT_10") (pintype "bidirectional"))
      (node (ref "DIP2") (pin "14") (pinfunction "OSC2/CLKO/RA6_14") (pintype "bidirectional"))
      (node (ref "J11") (pin "8") (pinfunction "8_8") (pintype "passive"))
      (node (ref "J12") (pin "8") (pinfunction "8_8") (pintype "passive"))
      (node (ref "J13") (pin "8") (pinfunction "8_8") (pintype "passive"))
      (node (ref "J4") (pin "8") (pinfunction "8_8") (pintype "passive"))
      (node (ref "SW1") (pin "6") (pinfunction "6_6") (pintype "passive"))
    )
    (net (code "24") (name "/RA7") (class "Default")
      (node (ref "DIP1") (pin "9") (pinfunction "RA7/OSC1/CLKIN_9") (pintype "bidirectional"))
      (node (ref "DIP2") (pin "13") (pinfunction "OSC1/CLKI/RA7_13") (pintype "bidirectional"))
      (node (ref "J11") (pin "7") (pinfunction "7_7") (pintype "passive"))
      (node (ref "J12") (pin "7") (pinfunction "7_7") (pintype "passive"))
      (node (ref "J13") (pin "7") (pinfunction "7_7") (pintype "passive"))
      (node (ref "J4") (pin "7") (pinfunction "7_7") (pintype "passive"))
      (node (ref "SW1") (pin "5") (pinfunction "5_5") (pintype "passive"))
    )
    (net (code "25") (name "/RB2") (class "Default")
      (node (ref "D8") (pin "1") (pinfunction "A_1") (pintype "passive"))
      (node (ref "DIP1") (pin "23") (pinfunction "RB2/AN8/P1B_23") (pintype "bidirectional"))
      (node (ref "DIP2") (pin "35") (pinfunction "RB2/INT2/AN8_35") (pintype "bidirectional"))
      (node (ref "J11") (pin "12") (pinfunction "12_12") (pintype "passive"))
      (node (ref "J12") (pin "12") (pinfunction "12_12") (pintype "passive"))
      (node (ref "J13") (pin "12") (pinfunction "12_12") (pintype "passive"))
      (node (ref "J5") (pin "4") (pinfunction "4_4") (pintype "passive"))
      (node (ref "LCD1") (pin "4") (pinfunction "RS_4") (pintype "passive"))
    )
    (net (code "26") (name "/RB3") (class "Default")
      (node (ref "D9") (pin "1") (pinfunction "A_1") (pintype "passive"))
      (node (ref "DIP1") (pin "24") (pinfunction "RB3/AN9/PGM/C12IN2-_24") (pintype "bidirectional"))
      (node (ref "DIP2") (pin "36") (pinfunction "RB3/AN9/CCP2_36") (pintype "bidirectional"))
      (node (ref "J11") (pin "11") (pinfunction "11_11") (pintype "passive"))
      (node (ref "J12") (pin "11") (pinfunction "11_11") (pintype "passive"))
      (node (ref "J13") (pin "11") (pinfunction "11_11") (pintype "passive"))
      (node (ref "J5") (pin "3") (pinfunction "3_3") (pintype "passive"))
      (node (ref "LCD1") (pin "6") (pinfunction "EN_6") (pintype "passive"))
    )
    (net (code "27") (name "/RB4") (class "Default")
      (node (ref "D10") (pin "1") (pinfunction "A_1") (pintype "passive"))
      (node (ref "DIP1") (pin "25") (pinfunction "RB4/AN11/P1D_25") (pintype "bidirectional"))
      (node (ref "DIP2") (pin "37") (pinfunction "RB4/KBI0/AN11_37") (pintype "bidirectional"))
      (node (ref "J11") (pin "14") (pinfunction "14_14") (pintype "passive"))
      (node (ref "J12") (pin "14") (pinfunction "14_14") (pintype "passive"))
      (node (ref "J13") (pin "14") (pinfunction "14_14") (pintype "passive"))
      (node (ref "J5") (pin "6") (pinfunction "6_6") (pintype "passive"))
      (node (ref "LCD1") (pin "11") (pinfunction "D4_11") (pintype "passive"))
    )
    (net (code "28") (name "/RB5") (class "Default")
      (node (ref "D11") (pin "1") (pinfunction "A_1") (pintype "passive"))
      (node (ref "DIP1") (pin "26") (pinfunction "RB5/AN13/~{T1G}_26") (pintype "bidirectional"))
      (node (ref "DIP2") (pin "38") (pinfunction "RB5/KBI1/PGM_38") (pintype "bidirectional"))
      (node (ref "J11") (pin "13") (pinfunction "13_13") (pintype "passive"))
      (node (ref "J12") (pin "13") (pinfunction "13_13") (pintype "passive"))
      (node (ref "J13") (pin "13") (pinfunction "13_13") (pintype "passive"))
      (node (ref "J5") (pin "5") (pinfunction "5_5") (pintype "passive"))
      (node (ref "LCD1") (pin "12") (pinfunction "D5_12") (pintype "passive"))
    )
    (net (code "29") (name "/RB6") (class "Default")
      (node (ref "D12") (pin "1") (pinfunction "A_1") (pintype "passive"))
      (node (ref "DIP1") (pin "27") (pinfunction "RB6/ICSPCLK_27") (pintype "bidirectional"))
      (node (ref "DIP2") (pin "39") (pinfunction "RB6/KBI2/PGC_39") (pintype "bidirectional"))
      (node (ref "J11") (pin "16") (pinfunction "16_16") (pintype "passive"))
      (node (ref "J12") (pin "16") (pinfunction "16_16") (pintype "passive"))
      (node (ref "J13") (pin "16") (pinfunction "16_16") (pintype "passive"))
      (node (ref "J21") (pin "5") (pinfunction "5_5") (pintype "passive"))
      (node (ref "J5") (pin "8") (pinfunction "8_8") (pintype "passive"))
      (node (ref "LCD1") (pin "13") (pinfunction "D6_13") (pintype "passive"))
      (node (ref "SW2") (pin "1") (pinfunction "1_1") (pintype "passive"))
    )
    (net (code "30") (name "/RB7") (class "Default")
      (node (ref "D13") (pin "1") (pinfunction "A_1") (pintype "passive"))
      (node (ref "DIP1") (pin "28") (pinfunction "RB7/ICSPDAT_28") (pintype "bidirectional"))
      (node (ref "DIP2") (pin "40") (pinfunction "RB7/KBI3/PGD_40") (pintype "bidirectional"))
      (node (ref "J11") (pin "15") (pinfunction "15_15") (pintype "passive"))
      (node (ref "J12") (pin "15") (pinfunction "15_15") (pintype "passive"))
      (node (ref "J13") (pin "15") (pinfunction "15_15") (pintype "passive"))
      (node (ref "J21") (pin "4") (pinfunction "4_4") (pintype "passive"))
      (node (ref "J5") (pin "7") (pinfunction "7_7") (pintype "passive"))
      (node (ref "LCD1") (pin "14") (pinfunction "D7_14") (pintype "passive"))
      (node (ref "SW2") (pin "2") (pinfunction "2_2") (pintype "passive"))
    )
    (net (code "31") (name "/RC0") (class "Default")
      (node (ref "DIP1") (pin "11") (pinfunction "RC0/T1OSO/T1CKI_11") (pintype "bidirectional"))
      (node (ref "DIP2") (pin "15") (pinfunction "RC0/T1OSO/T13CKI_15") (pintype "bidirectional"))
      (node (ref "J11") (pin "18") (pinfunction "18_18") (pintype "passive"))
      (node (ref "J12") (pin "18") (pinfunction "18_18") (pintype "passive"))
      (node (ref "J13") (pin "18") (pinfunction "18_18") (pintype "passive"))
      (node (ref "J6") (pin "2") (pinfunction "2_2") (pintype "passive"))
      (node (ref "R55") (pin "2") (pinfunction "2_2") (pintype "passive"))
      (node (ref "SW11") (pin "1") (pinfunction "1_1") (pintype "passive"))
      (node (ref "SW11") (pin "4") (pinfunction "2_4") (pintype "passive"))
      (node (ref "SW15") (pin "1") (pinfunction "1_1") (pintype "passive"))
      (node (ref "SW15") (pin "4") (pinfunction "2_4") (pintype "passive"))
      (node (ref "SW19") (pin "1") (pinfunction "1_1") (pintype "passive"))
      (node (ref "SW19") (pin "4") (pinfunction "2_4") (pintype "passive"))
      (node (ref "SW23") (pin "1") (pinfunction "1_1") (pintype "passive"))
      (node (ref "SW23") (pin "4") (pinfunction "2_4") (pintype "passive"))
    )
    (net (code "32") (name "/RC1") (class "Default")
      (node (ref "DIP1") (pin "12") (pinfunction "RC1/T1OSI/CCP2_12") (pintype "bidirectional"))
      (node (ref "DIP2") (pin "16") (pinfunction "RC1/T1OSI/CCP2_16") (pintype "bidirectional"))
      (node (ref "J11") (pin "17") (pinfunction "17_17") (pintype "passive"))
      (node (ref "J12") (pin "17") (pinfunction "17_17") (pintype "passive"))
      (node (ref "J13") (pin "17") (pinfunction "17_17") (pintype "passive"))
      (node (ref "J6") (pin "1") (pinfunction "1_1") (pintype "passive"))
      (node (ref "R56") (pin "2") (pinfunction "2_2") (pintype "passive"))
      (node (ref "SW12") (pin "1") (pinfunction "1_1") (pintype "passive"))
      (node (ref "SW12") (pin "4") (pinfunction "2_4") (pintype "passive"))
      (node (ref "SW16") (pin "1") (pinfunction "1_1") (pintype "passive"))
      (node (ref "SW16") (pin "4") (pinfunction "2_4") (pintype "passive"))
      (node (ref "SW20") (pin "1") (pinfunction "1_1") (pintype "passive"))
      (node (ref "SW20") (pin "4") (pinfunction "2_4") (pintype "passive"))
      (node (ref "SW24") (pin "1") (pinfunction "1_1") (pintype "passive"))
      (node (ref "SW24") (pin "4") (pinfunction "2_4") (pintype "passive"))
    )
    (net (code "33") (name "/RC2") (class "Default")
      (node (ref "DIP1") (pin "13") (pinfunction "RC2/P1A/CCP1_13") (pintype "bidirectional"))
      (node (ref "DIP2") (pin "17") (pinfunction "RC2/CCP1/P1A_17") (pintype "bidirectional"))
      (node (ref "J11") (pin "22") (pinfunction "22_22") (pintype "passive"))
      (node (ref "J12") (pin "22") (pinfunction "22_22") (pintype "passive"))
      (node (ref "J13") (pin "22") (pinfunction "22_22") (pintype "passive"))
      (node (ref "J6") (pin "4") (pinfunction "4_4") (pintype "passive"))
      (node (ref "R47") (pin "1") (pinfunction "1_1") (pintype "passive"))
      (node (ref "R57") (pin "2") (pinfunction "2_2") (pintype "passive"))
      (node (ref "SW13") (pin "1") (pinfunction "1_1") (pintype "passive"))
      (node (ref "SW13") (pin "4") (pinfunction "2_4") (pintype "passive"))
      (node (ref "SW17") (pin "1") (pinfunction "1_1") (pintype "passive"))
      (node (ref "SW17") (pin "4") (pinfunction "2_4") (pintype "passive"))
      (node (ref "SW21") (pin "1") (pinfunction "1_1") (pintype "passive"))
      (node (ref "SW21") (pin "4") (pinfunction "2_4") (pintype "passive"))
      (node (ref "SW25") (pin "1") (pinfunction "1_1") (pintype "passive"))
      (node (ref "SW25") (pin "4") (pinfunction "2_4") (pintype "passive"))
    )
    (net (code "34") (name "/RC3") (class "Default")
      (node (ref "DIP1") (pin "14") (pinfunction "RC3/SCK/SCL_14") (pintype "bidirectional"))
      (node (ref "DIP2") (pin "18") (pinfunction "RC3/SCK/SCL_18") (pintype "bidirectional"))
      (node (ref "J11") (pin "21") (pinfunction "21_21") (pintype "passive"))
      (node (ref "J12") (pin "21") (pinfunction "21_21") (pintype "passive"))
      (node (ref "J13") (pin "21") (pinfunction "21_21") (pintype "passive"))
      (node (ref "J6") (pin "3") (pinfunction "3_3") (pintype "passive"))
      (node (ref "R58") (pin "2") (pinfunction "2_2") (pintype "passive"))
      (node (ref "SW14") (pin "1") (pinfunction "1_1") (pintype "passive"))
      (node (ref "SW14") (pin "4") (pinfunction "2_4") (pintype "passive"))
      (node (ref "SW18") (pin "1") (pinfunction "1_1") (pintype "passive"))
      (node (ref "SW18") (pin "4") (pinfunction "2_4") (pintype "passive"))
      (node (ref "SW22") (pin "1") (pinfunction "1_1") (pintype "passive"))
      (node (ref "SW22") (pin "4") (pinfunction "2_4") (pintype "passive"))
      (node (ref "SW26") (pin "1") (pinfunction "1_1") (pintype "passive"))
      (node (ref "SW26") (pin "4") (pinfunction "2_4") (pintype "passive"))
      (node (ref "SW3") (pin "1") (pinfunction "1_1") (pintype "passive"))
      (node (ref "SW4") (pin "2") (pinfunction "2_2") (pintype "passive"))
    )
    (net (code "35") (name "/RC4") (class "Default")
      (node (ref "DIP1") (pin "15") (pinfunction "RC4/SDI/SDA_15") (pintype "bidirectional"))
      (node (ref "DIP2") (pin "23") (pinfunction "RC4/SDI/SDA_23") (pintype "bidirectional"))
      (node (ref "J11") (pin "24") (pinfunction "24_24") (pintype "passive"))
      (node (ref "J12") (pin "24") (pinfunction "24_24") (pintype "passive"))
      (node (ref "J13") (pin "24") (pinfunction "24_24") (pintype "passive"))
      (node (ref "J2") (pin "2") (pinfunction "D-_2") (pintype "input"))
      (node (ref "J6") (pin "6") (pinfunction "6_6") (pintype "passive"))
      (node (ref "SW11") (pin "2") (pinfunction "2_2") (pintype "passive"))
      (node (ref "SW11") (pin "3") (pinfunction "1_3") (pintype "passive"))
      (node (ref "SW12") (pin "2") (pinfunction "2_2") (pintype "passive"))
      (node (ref "SW12") (pin "3") (pinfunction "1_3") (pintype "passive"))
      (node (ref "SW13") (pin "2") (pinfunction "2_2") (pintype "passive"))
      (node (ref "SW13") (pin "3") (pinfunction "1_3") (pintype "passive"))
      (node (ref "SW14") (pin "2") (pinfunction "2_2") (pintype "passive"))
      (node (ref "SW14") (pin "3") (pinfunction "1_3") (pintype "passive"))
      (node (ref "SW4") (pin "3") (pinfunction "3_3") (pintype "passive"))
    )
    (net (code "36") (name "/RC5") (class "Default")
      (node (ref "DIP1") (pin "16") (pinfunction "RC5/SDO_16") (pintype "bidirectional"))
      (node (ref "DIP2") (pin "24") (pinfunction "RC5/SDO_24") (pintype "bidirectional"))
      (node (ref "J11") (pin "23") (pinfunction "23_23") (pintype "passive"))
      (node (ref "J12") (pin "23") (pinfunction "23_23") (pintype "passive"))
      (node (ref "J13") (pin "23") (pinfunction "23_23") (pintype "passive"))
      (node (ref "J2") (pin "3") (pinfunction "D+_3") (pintype "input"))
      (node (ref "J6") (pin "5") (pinfunction "5_5") (pintype "passive"))
      (node (ref "SW15") (pin "2") (pinfunction "2_2") (pintype "passive"))
      (node (ref "SW15") (pin "3") (pinfunction "1_3") (pintype "passive"))
      (node (ref "SW16") (pin "2") (pinfunction "2_2") (pintype "passive"))
      (node (ref "SW16") (pin "3") (pinfunction "1_3") (pintype "passive"))
      (node (ref "SW17") (pin "2") (pinfunction "2_2") (pintype "passive"))
      (node (ref "SW17") (pin "3") (pinfunction "1_3") (pintype "passive"))
      (node (ref "SW18") (pin "2") (pinfunction "2_2") (pintype "passive"))
      (node (ref "SW18") (pin "3") (pinfunction "1_3") (pintype "passive"))
    )
    (net (code "37") (name "/RC6") (class "Default")
      (node (ref "DIP1") (pin "17") (pinfunction "RC6/TX/CK_17") (pintype "bidirectional"))
      (node (ref "DIP2") (pin "25") (pinfunction "RC6/TX/CK_25") (pintype "bidirectional"))
      (node (ref "J11") (pin "26") (pinfunction "26_26") (pintype "passive"))
      (node (ref "J12") (pin "26") (pinfunction "26_26") (pintype "passive"))
      (node (ref "J13") (pin "26") (pinfunction "26_26") (pintype "passive"))
      (node (ref "J6") (pin "8") (pinfunction "8_8") (pintype "passive"))
      (node (ref "R38") (pin "1") (pinfunction "1_1") (pintype "passive"))
      (node (ref "SW19") (pin "2") (pinfunction "2_2") (pintype "passive"))
      (node (ref "SW19") (pin "3") (pinfunction "1_3") (pintype "passive"))
      (node (ref "SW20") (pin "2") (pinfunction "2_2") (pintype "passive"))
      (node (ref "SW20") (pin "3") (pinfunction "1_3") (pintype "passive"))
      (node (ref "SW21") (pin "2") (pinfunction "2_2") (pintype "passive"))
      (node (ref "SW21") (pin "3") (pinfunction "1_3") (pintype "passive"))
      (node (ref "SW22") (pin "2") (pinfunction "2_2") (pintype "passive"))
      (node (ref "SW22") (pin "3") (pinfunction "1_3") (pintype "passive"))
      (node (ref "U7") (pin "11") (pinfunction "DIN1_11") (pintype "passive"))
    )
    (net (code "38") (name "/RC7") (class "Default")
      (node (ref "DIP1") (pin "18") (pinfunction "RC7/RX/DT_18") (pintype "bidirectional"))
      (node (ref "DIP2") (pin "26") (pinfunction "RC7/RX/DT_26") (pintype "bidirectional"))
      (node (ref "J11") (pin "25") (pinfunction "25_25") (pintype "passive"))
      (node (ref "J12") (pin "25") (pinfunction "25_25") (pintype "passive"))
      (node (ref "J13") (pin "25") (pinfunction "25_25") (pintype "passive"))
      (node (ref "J6") (pin "7") (pinfunction "7_7") (pintype "passive"))
      (node (ref "SW23") (pin "2") (pinfunction "2_2") (pintype "passive"))
      (node (ref "SW23") (pin "3") (pinfunction "1_3") (pintype "passive"))
      (node (ref "SW24") (pin "2") (pinfunction "2_2") (pintype "passive"))
      (node (ref "SW24") (pin "3") (pinfunction "1_3") (pintype "passive"))
      (node (ref "SW25") (pin "2") (pinfunction "2_2") (pintype "passive"))
      (node (ref "SW25") (pin "3") (pinfunction "1_3") (pintype "passive"))
      (node (ref "SW26") (pin "2") (pinfunction "2_2") (pintype "passive"))
      (node (ref "SW26") (pin "3") (pinfunction "1_3") (pintype "passive"))
      (node (ref "U7") (pin "12") (pinfunction "ROUT1_12") (pintype "passive"))
    )
    (net (code "39") (name "/RD0") (class "Default")
      (node (ref "DIP2") (pin "19") (pinfunction "RD0/PSP0_19") (pintype "bidirectional"))
      (node (ref "J11") (pin "28") (pinfunction "28_28") (pintype "passive"))
      (node (ref "J12") (pin "28") (pinfunction "28_28") (pintype "passive"))
      (node (ref "J13") (pin "28") (pinfunction "28_28") (pintype "passive"))
      (node (ref "J7") (pin "2") (pinfunction "2_2") (pintype "passive"))
    )
    (net (code "40") (name "/RD1") (class "Default")
      (node (ref "DIP2") (pin "20") (pinfunction "RD1/PSP1_20") (pintype "bidirectional"))
      (node (ref "J11") (pin "27") (pinfunction "27_27") (pintype "passive"))
      (node (ref "J12") (pin "27") (pinfunction "27_27") (pintype "passive"))
      (node (ref "J13") (pin "27") (pinfunction "27_27") (pintype "passive"))
      (node (ref "J7") (pin "1") (pinfunction "1_1") (pintype "passive"))
    )
    (net (code "41") (name "/RD2") (class "Default")
      (node (ref "DIP2") (pin "21") (pinfunction "RD2/PSP2_21") (pintype "bidirectional"))
      (node (ref "J11") (pin "30") (pinfunction "30_30") (pintype "passive"))
      (node (ref "J12") (pin "30") (pinfunction "30_30") (pintype "passive"))
      (node (ref "J13") (pin "30") (pinfunction "30_30") (pintype "passive"))
      (node (ref "J7") (pin "4") (pinfunction "4_4") (pintype "passive"))
    )
    (net (code "42") (name "/RD3") (class "Default")
      (node (ref "DIP2") (pin "22") (pinfunction "RD3/PSP3_22") (pintype "bidirectional"))
      (node (ref "J11") (pin "29") (pinfunction "29_29") (pintype "passive"))
      (node (ref "J12") (pin "29") (pinfunction "29_29") (pintype "passive"))
      (node (ref "J13") (pin "29") (pinfunction "29_29") (pintype "passive"))
      (node (ref "J7") (pin "3") (pinfunction "3_3") (pintype "passive"))
    )
    (net (code "43") (name "/RD4") (class "Default")
      (node (ref "DIP2") (pin "27") (pinfunction "RD4/PSP4_27") (pintype "bidirectional"))
      (node (ref "J11") (pin "32") (pinfunction "32_32") (pintype "passive"))
      (node (ref "J12") (pin "32") (pinfunction "32_32") (pintype "passive"))
      (node (ref "J13") (pin "32") (pinfunction "32_32") (pintype "passive"))
      (node (ref "J7") (pin "6") (pinfunction "6_6") (pintype "passive"))
    )
    (net (code "44") (name "/RD5") (class "Default")
      (node (ref "DIP2") (pin "28") (pinfunction "RD5/PSP5/P1B_28") (pintype "bidirectional"))
      (node (ref "J11") (pin "31") (pinfunction "31_31") (pintype "passive"))
      (node (ref "J12") (pin "31") (pinfunction "31_31") (pintype "passive"))
      (node (ref "J13") (pin "31") (pinfunction "31_31") (pintype "passive"))
      (node (ref "J7") (pin "5") (pinfunction "5_5") (pintype "passive"))
    )
    (net (code "45") (name "/RD6") (class "Default")
      (node (ref "DIP2") (pin "29") (pinfunction "RD6/PSP6/P1C_29") (pintype "bidirectional"))
      (node (ref "J11") (pin "34") (pinfunction "34_34") (pintype "passive"))
      (node (ref "J12") (pin "34") (pinfunction "34_34") (pintype "passive"))
      (node (ref "J13") (pin "34") (pinfunction "34_34") (pintype "passive"))
      (node (ref "J7") (pin "8") (pinfunction "8_8") (pintype "passive"))
    )
    (net (code "46") (name "/RD7") (class "Default")
      (node (ref "DIP2") (pin "30") (pinfunction "RD7/PSP7/P1D_30") (pintype "bidirectional"))
      (node (ref "J11") (pin "33") (pinfunction "33_33") (pintype "passive"))
      (node (ref "J12") (pin "33") (pinfunction "33_33") (pintype "passive"))
      (node (ref "J13") (pin "33") (pinfunction "33_33") (pintype "passive"))
      (node (ref "J7") (pin "7") (pinfunction "7_7") (pintype "passive"))
    )
    (net (code "47") (name "/RE0") (class "Default")
      (node (ref "DIP2") (pin "8") (pinfunction "RE0/~{RD}/AN5_8") (pintype "bidirectional"))
      (node (ref "J11") (pin "36") (pinfunction "36_36") (pintype "passive"))
      (node (ref "J12") (pin "36") (pinfunction "36_36") (pintype "passive"))
      (node (ref "J13") (pin "36") (pinfunction "36_36") (pintype "passive"))
      (node (ref "J8") (pin "2") (pinfunction "2_2") (pintype "passive"))
    )
    (net (code "48") (name "/RE1") (class "Default")
      (node (ref "DIP2") (pin "9") (pinfunction "RE1/~{WR}/AN6_9") (pintype "bidirectional"))
      (node (ref "J11") (pin "35") (pinfunction "35_35") (pintype "passive"))
      (node (ref "J12") (pin "35") (pinfunction "35_35") (pintype "passive"))
      (node (ref "J13") (pin "35") (pinfunction "35_35") (pintype "passive"))
      (node (ref "J8") (pin "1") (pinfunction "1_1") (pintype "passive"))
    )
    (net (code "49") (name "/RE2") (class "Default")
      (node (ref "DIP2") (pin "10") (pinfunction "RE2/~{CS}/AN7_10") (pintype "bidirectional"))
      (node (ref "J11") (pin "38") (pinfunction "38_38") (pintype "passive"))
      (node (ref "J12") (pin "38") (pinfunction "38_38") (pintype "passive"))
      (node (ref "J13") (pin "38") (pinfunction "38_38") (pintype "passive"))
      (node (ref "J8") (pin "4") (pinfunction "4_4") (pintype "passive"))
    )
    (net (code "50") (name "/RE3") (class "Default")
      (node (ref "DIP1") (pin "1") (pinfunction "RE3/~{MCLR}/VPP_1") (pintype "bidirectional"))
      (node (ref "DIP2") (pin "1") (pinfunction "~{MCLR}/VPP/RE3_1") (pintype "input"))
      (node (ref "J11") (pin "37") (pinfunction "37_37") (pintype "passive"))
      (node (ref "J12") (pin "37") (pinfunction "37_37") (pintype "passive"))
      (node (ref "J13") (pin "37") (pinfunction "37_37") (pintype "passive"))
      (node (ref "J21") (pin "1") (pinfunction "1_1") (pintype "passive"))
      (node (ref "J8") (pin "3") (pinfunction "3_3") (pintype "passive"))
      (node (ref "SW1") (pin "1") (pinfunction "1_1") (pintype "passive"))
      (node (ref "SW2") (pin "4") (pinfunction "4_4") (pintype "passive"))
    )
    (net (code "51") (name "/RTC_SCL") (class "Default")
      (node (ref "R48") (pin "1") (pinfunction "1_1") (pintype "passive"))
      (node (ref "SW4") (pin "7") (pinfunction "7_7") (pintype "passive"))
      (node (ref "U6") (pin "6") (pinfunction "SCL_6") (pintype "passive"))
    )
    (net (code "52") (name "/RTC_SDA") (class "Default")
      (node (ref "R49") (pin "1") (pinfunction "1_1") (pintype "passive"))
      (node (ref "SW4") (pin "6") (pinfunction "6_6") (pintype "passive"))
      (node (ref "U6") (pin "5") (pinfunction "SDA_5") (pintype "passive"))
    )
    (net (code "53") (name "/RxIN") (class "Default")
      (node (ref "P1") (pin "3") (pinfunction "3_3") (pintype "passive"))
      (node (ref "U7") (pin "13") (pinfunction "RIN1_13") (pintype "passive"))
    )
    (net (code "54") (name "/TxOUT") (class "Default")
      (node (ref "P1") (pin "2") (pinfunction "2_2") (pintype "passive"))
      (node (ref "U7") (pin "14") (pinfunction "DOUT1_14") (pintype "passive"))
    )
    (net (code "55") (name "/USB_D+") (class "Default")
      (node (ref "J3") (pin "3") (pinfunction "D+_3") (pintype "input"))
      (node (ref "U1") (pin "16") (pinfunction "RC5/D+/VP_16") (pintype "bidirectional"))
    )
    (net (code "56") (name "/USB_D-") (class "Default")
      (node (ref "J3") (pin "2") (pinfunction "D-_2") (pintype "input"))
      (node (ref "U1") (pin "15") (pinfunction "RC4/D-/VM_15") (pintype "bidirectional"))
    )
    (net (code "57") (name "/VCC_LCD") (class "Default")
      (node (ref "LCD1") (pin "2") (pinfunction "VDD_2") (pintype "passive"))
      (node (ref "R18") (pin "1") (pinfunction "1_1") (pintype "passive"))
      (node (ref "R52") (pin "1") (pinfunction "1_1") (pintype "passive"))
      (node (ref "SW3") (pin "4") (pinfunction "4_4") (pintype "passive"))
    )
    (net (code "58") (name "/VCC_MOTOR") (class "Default")
      (node (ref "C4") (pin "1") (pinfunction "1_1") (pintype "passive"))
      (node (ref "D14") (pin "2") (pinfunction "K_2") (pintype "passive"))
      (node (ref "MG1") (pin "1") (pinfunction "+_1") (pintype "passive"))
      (node (ref "SW4") (pin "8") (pinfunction "8_8") (pintype "passive"))
    )
    (net (code "59") (name "/VCC_PS2") (class "Default")
      (node (ref "R40") (pin "2") (pinfunction "2_2") (pintype "passive"))
      (node (ref "R41") (pin "2") (pinfunction "2_2") (pintype "passive"))
      (node (ref "SW3") (pin "2") (pinfunction "2_2") (pintype "passive"))
    )
    (net (code "60") (name "/VCC_UART") (class "Default")
      (node (ref "C31") (pin "2") (pinfunction "2_2") (pintype "passive"))
      (node (ref "R38") (pin "2") (pinfunction "2_2") (pintype "passive"))
      (node (ref "SW3") (pin "3") (pinfunction "3_3") (pintype "passive"))
      (node (ref "U7") (pin "16") (pinfunction "VCC_16") (pintype "passive"))
    )
    (net (code "61") (name "/VDD_TGT_ADJ") (class "Default")
      (node (ref "R4") (pin "2") (pinfunction "2_2") (pintype "passive"))
      (node (ref "U1") (pin "13") (pinfunction "RC2/CCP1_13") (pintype "bidirectional"))
    )
    (net (code "62") (name "/VDD_TGT_FB") (class "Default")
      (node (ref "R26") (pin "2") (pinfunction "2_2") (pintype "passive"))
      (node (ref "U1") (pin "3") (pinfunction "RA1/AN1_3") (pintype "bidirectional"))
    )
    (net (code "63") (name "/VDD_TGT_N") (class "Default")
      (node (ref "R12") (pin "1") (pinfunction "1_1") (pintype "passive"))
      (node (ref "U1") (pin "24") (pinfunction "RB3/AN9/CCP2/VPO_24") (pintype "bidirectional"))
      (node (ref "U5") (pin "1") (pinfunction "G_1") (pintype "passive"))
    )
    (net (code "64") (name "/VDD_TGT_OUTPUT") (class "Default")
      (node (ref "D2") (pin "A") (pinfunction "A_A") (pintype "passive"))
      (node (ref "D4") (pin "1") (pinfunction "K_1") (pintype "passive"))
      (node (ref "J22") (pin "2") (pinfunction "2_2") (pintype "passive"))
      (node (ref "R13") (pin "2") (pinfunction "2_2") (pintype "passive"))
      (node (ref "R26") (pin "1") (pinfunction "1_1") (pintype "passive"))
      (node (ref "SW2") (pin "6") (pinfunction "6_6") (pintype "passive"))
    )
    (net (code "65") (name "/VDD_TGT_P") (class "Default")
      (node (ref "D17") (pin "1") (pinfunction "A_1") (pintype "passive"))
      (node (ref "R16") (pin "2") (pinfunction "2_2") (pintype "passive"))
      (node (ref "R30") (pin "1") (pinfunction "1_1") (pintype "passive"))
      (node (ref "U1") (pin "25") (pinfunction "RB4/AN11/KBI0_25") (pintype "bidirectional"))
    )
    (net (code "66") (name "/VPP_FEEDBACK") (class "Default")
      (node (ref "R22") (pin "1") (pinfunction "1_1") (pintype "passive"))
      (node (ref "R24") (pin "2") (pinfunction "2_2") (pintype "passive"))
      (node (ref "U1") (pin "2") (pinfunction "RA0/AN0_2") (pintype "bidirectional"))
    )
    (net (code "67") (name "/VPP_ON") (class "Default")
      (node (ref "R27") (pin "2") (pinfunction "2_2") (pintype "passive"))
      (node (ref "U1") (pin "23") (pinfunction "RB2/AN8/INT2/VMO_23") (pintype "bidirectional"))
    )
    (net (code "68") (name "/VPP_OUTPUT") (class "Default")
      (node (ref "J22") (pin "1") (pinfunction "1_1") (pintype "passive"))
      (node (ref "Q6") (pin "3") (pinfunction "C_3") (pintype "passive"))
      (node (ref "R28") (pin "2") (pinfunction "2_2") (pintype "passive"))
      (node (ref "SW2") (pin "5") (pinfunction "5_5") (pintype "passive"))
    )
    (net (code "69") (name "/VPP_PUMP") (class "Default")
      (node (ref "R21") (pin "1") (pinfunction "1_1") (pintype "passive"))
      (node (ref "U1") (pin "12") (pinfunction "RC1/T1OSI/CCP2/~{UOE}_12") (pintype "bidirectional"))
    )
    (net (code "70") (name "/_SCL") (class "Default")
      (node (ref "R8") (pin "1") (pinfunction "1_1") (pintype "passive"))
      (node (ref "U1") (pin "22") (pinfunction "RB1/AN10/INT1/SCK/SCL_22") (pintype "bidirectional"))
    )
    (net (code "71") (name "/_SDA") (class "Default")
      (node (ref "R9") (pin "1") (pinfunction "1_1") (pintype "passive"))
      (node (ref "U1") (pin "21") (pinfunction "RB0/AN12/INT0/FLT0/SDI/SDA_21") (pintype "bidirectional"))
    )
    (net (code "72") (name "GND") (class "Default")
      (node (ref "BT1") (pin "2") (pinfunction "GND_2") (pintype "passive"))
      (node (ref "C1") (pin "2") (pinfunction "2_2") (pintype "passive"))
      (node (ref "C11") (pin "2") (pinfunction "2_2") (pintype "passive"))
      (node (ref "C12") (pin "2") (pinfunction "2_2") (pintype "passive"))
      (node (ref "C13") (pin "2") (pinfunction "2_2") (pintype "passive"))
      (node (ref "C14") (pin "2") (pinfunction "2_2") (pintype "passive"))
      (node (ref "C15") (pin "2") (pinfunction "2_2") (pintype "passive"))
      (node (ref "C17") (pin "2") (pinfunction "2_2") (pintype "passive"))
      (node (ref "C18") (pin "2") (pinfunction "2_2") (pintype "passive"))
      (node (ref "C19") (pin "2") (pinfunction "2_2") (pintype "passive"))
      (node (ref "C2") (pin "2") (pinfunction "2_2") (pintype "passive"))
      (node (ref "C20") (pin "2") (pinfunction "2_2") (pintype "passive"))
      (node (ref "C21") (pin "2") (pinfunction "2_2") (pintype "passive"))
      (node (ref "C22") (pin "2") (pinfunction "2_2") (pintype "passive"))
      (node (ref "C23") (pin "2") (pinfunction "2_2") (pintype "passive"))
      (node (ref "C24") (pin "2") (pinfunction "2_2") (pintype "passive"))
      (node (ref "C26") (pin "1") (pinfunction "1_1") (pintype "passive"))
      (node (ref "C27") (pin "2") (pinfunction "2_2") (pintype "passive"))
      (node (ref "C28") (pin "2") (pinfunction "2_2") (pintype "passive"))
      (node (ref "C3") (pin "2") (pinfunction "2_2") (pintype "passive"))
      (node (ref "C32") (pin "1") (pinfunction "1_1") (pintype "passive"))
      (node (ref "C33") (pin "2") (pinfunction "2_2") (pintype "passive"))
      (node (ref "C34") (pin "1") (pinfunction "1_1") (pintype "passive"))
      (node (ref "C4") (pin "2") (pinfunction "2_2") (pintype "passive"))
      (node (ref "C5") (pin "1") (pinfunction "1_1") (pintype "passive"))
      (node (ref "C6") (pin "1") (pinfunction "1_1") (pintype "passive"))
      (node (ref "C7") (pin "1") (pinfunction "1_1") (pintype "passive"))
      (node (ref "C8") (pin "1") (pinfunction "1_1") (pintype "passive"))
      (node (ref "D1") (pin "4") (pinfunction "-V_OUT_4") (pintype "passive"))
      (node (ref "D15") (pin "2") (pinfunction "K_2") (pintype "passive"))
      (node (ref "DIP1") (pin "19") (pinfunction "VSS_19") (pintype "power_in"))
      (node (ref "DIP1") (pin "8") (pinfunction "VSS_8") (pintype "power_in"))
      (node (ref "DIP2") (pin "12") (pinfunction "VSS_12") (pintype "power_in"))
      (node (ref "DIP2") (pin "31") (pinfunction "VSS_31") (pintype "power_in"))
      (node (ref "J11") (pin "19") (pinfunction "19_19") (pintype "passive"))
      (node (ref "J11") (pin "39") (pinfunction "39_39") (pintype "passive"))
      (node (ref "J12") (pin "19") (pinfunction "19_19") (pintype "passive"))
      (node (ref "J12") (pin "39") (pinfunction "39_39") (pintype "passive"))
      (node (ref "J13") (pin "19") (pinfunction "19_19") (pintype "passive"))
      (node (ref "J13") (pin "39") (pinfunction "39_39") (pintype "passive"))
      (node (ref "J14") (pin "3") (pinfunction "3_3") (pintype "passive"))
      (node (ref "J2") (pin "4") (pinfunction "GND_4") (pintype "power_in"))
      (node (ref "J21") (pin "3") (pinfunction "3_3") (pintype "passive"))
      (node (ref "J22") (pin "3") (pinfunction "3_3") (pintype "passive"))
      (node (ref "J3") (pin "4") (pinfunction "GND_4") (pintype "power_in"))
      (node (ref "J4") (pin "9") (pinfunction "9_9") (pintype "passive"))
      (node (ref "J5") (pin "9") (pinfunction "9_9") (pintype "passive"))
      (node (ref "J6") (pin "9") (pinfunction "9_9") (pintype "passive"))
      (node (ref "J7") (pin "9") (pinfunction "9_9") (pintype "passive"))
      (node (ref "J8") (pin "9") (pinfunction "9_9") (pintype "passive"))
      (node (ref "LCD1") (pin "1") (pinfunction "VSS_1") (pintype "passive"))
      (node (ref "LCD1") (pin "16") (pinfunction "LED-_16") (pintype "passive"))
      (node (ref "LCD1") (pin "5") (pinfunction "RD_5") (pintype "passive"))
      (node (ref "P1") (pin "5") (pinfunction "5_5") (pintype "passive"))
      (node (ref "Q2") (pin "3") (pinfunction "C_3") (pintype "passive"))
      (node (ref "Q3") (pin "3") (pinfunction "C_3") (pintype "passive"))
      (node (ref "Q4") (pin "2") (pinfunction "E_2") (pintype "passive"))
      (node (ref "Q5") (pin "3") (pinfunction "C_3") (pintype "passive"))
      (node (ref "Q7") (pin "2") (pinfunction "E_2") (pintype "passive"))
      (node (ref "Q8") (pin "2") (pinfunction "E_2") (pintype "passive"))
      (node (ref "R12") (pin "2") (pinfunction "2_2") (pintype "passive"))
      (node (ref "R17") (pin "1") (pinfunction "1_1") (pintype "passive"))
      (node (ref "R24") (pin "1") (pinfunction "1_1") (pintype "passive"))
      (node (ref "R3") (pin "1") (pinfunction "1_1") (pintype "passive"))
      (node (ref "R34") (pin "1") (pinfunction "1_1") (pintype "passive"))
      (node (ref "R35") (pin "1") (pinfunction "1_1") (pintype "passive"))
      (node (ref "R36") (pin "1") (pinfunction "1_1") (pintype "passive"))
      (node (ref "R37") (pin "1") (pinfunction "1_1") (pintype "passive"))
      (node (ref "R43") (pin "1") (pinfunction "1_1") (pintype "passive"))
      (node (ref "R52") (pin "3") (pinfunction "3_3") (pintype "passive"))
      (node (ref "R54") (pin "1") (pinfunction "1_1") (pintype "passive"))
      (node (ref "R6") (pin "1") (pinfunction "1_1") (pintype "passive"))
      (node (ref "R7") (pin "1") (pinfunction "1_1") (pintype "passive"))
      (node (ref "REG1") (pin "2") (pinfunction "GND_2") (pintype "passive"))
      (node (ref "SW1") (pin "7") (pinfunction "7_7") (pintype "passive"))
      (node (ref "SW6") (pin "1") (pinfunction "1_1") (pintype "passive"))
      (node (ref "U1") (pin "19") (pinfunction "VSS_19") (pintype "power_in"))
      (node (ref "U1") (pin "8") (pinfunction "VSS_8") (pintype "power_in"))
      (node (ref "U2") (pin "4") (pinfunction "GND_4") (pintype "passive"))
      (node (ref "U5") (pin "5") (pinfunction "S_5") (pintype "passive"))
      (node (ref "U6") (pin "4") (pinfunction "GND_4") (pintype "passive"))
      (node (ref "U7") (pin "15") (pinfunction "GND_15") (pintype "passive"))
    )
    (net (code "73") (name "Net-(BT1-VCC)") (class "Default")
      (node (ref "BT1") (pin "1") (pinfunction "VCC_1") (pintype "passive"))
      (node (ref "U6") (pin "3") (pinfunction "VBAT_3") (pintype "passive"))
    )
    (net (code "74") (name "Net-(C26-Pad2)") (class "Default")
      (node (ref "C26") (pin "2") (pinfunction "2_2") (pintype "passive"))
      (node (ref "C6") (pin "2") (pinfunction "2_2") (pintype "passive"))
      (node (ref "SW1") (pin "3") (pinfunction "3_3") (pintype "passive"))
      (node (ref "Y1") (pin "2") (pinfunction "2_2") (pintype "passive"))
    )
    (net (code "75") (name "Net-(C27-Pad1)") (class "Default")
      (node (ref "C27") (pin "1") (pinfunction "1_1") (pintype "passive"))
      (node (ref "C28") (pin "1") (pinfunction "1_1") (pintype "passive"))
      (node (ref "SW3") (pin "8") (pinfunction "8_8") (pintype "passive"))
    )
    (net (code "76") (name "Net-(C34-Pad2)") (class "Default")
      (node (ref "C34") (pin "2") (pinfunction "2_2") (pintype "passive"))
      (node (ref "C5") (pin "2") (pinfunction "2_2") (pintype "passive"))
      (node (ref "SW1") (pin "4") (pinfunction "4_4") (pintype "passive"))
      (node (ref "Y1") (pin "1") (pinfunction "1_1") (pintype "passive"))
    )
    (net (code "77") (name "Net-(D1-+V_OUT)") (class "Default")
      (node (ref "C1") (pin "1") (pinfunction "1_1") (pintype "passive"))
      (node (ref "D1") (pin "1") (pinfunction "+V_OUT_1") (pintype "passive"))
      (node (ref "REG1") (pin "1") (pinfunction "Vin_1") (pintype "power_in"))
    )
    (net (code "78") (name "Net-(D1-AC1)") (class "Default")
      (node (ref "D1") (pin "2") (pinfunction "AC1_2") (pintype "passive"))
      (node (ref "J1") (pin "2") (pinfunction "TN_2") (pintype "passive"))
    )
    (net (code "79") (name "Net-(D1-AC2)") (class "Default")
      (node (ref "D1") (pin "3") (pinfunction "AC2_3") (pintype "passive"))
      (node (ref "J1") (pin "1") (pinfunction "T_1") (pintype "passive"))
    )
    (net (code "80") (name "Net-(D3-A)") (class "Default")
      (node (ref "D3") (pin "1") (pinfunction "A_1") (pintype "passive"))
      (node (ref "L1") (pin "2") (pinfunction "2_2") (pintype "passive"))
      (node (ref "Q4") (pin "3") (pinfunction "C_3") (pintype "passive"))
    )
    (net (code "81") (name "Net-(D3-K)") (class "Default")
      (node (ref "C22") (pin "1") (pinfunction "1_1") (pintype "passive"))
      (node (ref "D3") (pin "2") (pinfunction "K_2") (pintype "passive"))
      (node (ref "Q6") (pin "2") (pinfunction "E_2") (pintype "passive"))
      (node (ref "R22") (pin "2") (pinfunction "2_2") (pintype "passive"))
      (node (ref "R23") (pin "2") (pinfunction "2_2") (pintype "passive"))
    )
    (net (code "82") (name "Net-(D4-A)") (class "Default")
      (node (ref "D4") (pin "3") (pinfunction "A_3") (pintype "passive"))
      (node (ref "U5") (pin "4") (pinfunction "D_4") (pintype "passive"))
    )
    (net (code "83") (name "Net-(D6-K)") (class "Default")
      (node (ref "D6") (pin "2") (pinfunction "K_2") (pintype "passive"))
      (node (ref "R44") (pin "2") (pinfunction "2_2") (pintype "passive"))
    )
    (net (code "84") (name "Net-(D7-K)") (class "Default")
      (node (ref "D7") (pin "2") (pinfunction "K_2") (pintype "passive"))
      (node (ref "R44") (pin "3") (pinfunction "3_3") (pintype "passive"))
    )
    (net (code "85") (name "Net-(D8-K)") (class "Default")
      (node (ref "D8") (pin "2") (pinfunction "K_2") (pintype "passive"))
      (node (ref "R44") (pin "4") (pinfunction "4_4") (pintype "passive"))
    )
    (net (code "86") (name "Net-(D9-K)") (class "Default")
      (node (ref "D9") (pin "2") (pinfunction "K_2") (pintype "passive"))
      (node (ref "R44") (pin "5") (pinfunction "5_5") (pintype "passive"))
    )
    (net (code "87") (name "Net-(D10-K)") (class "Default")
      (node (ref "D10") (pin "2") (pinfunction "K_2") (pintype "passive"))
      (node (ref "R44") (pin "6") (pinfunction "6_6") (pintype "passive"))
    )
    (net (code "88") (name "Net-(D11-K)") (class "Default")
      (node (ref "D11") (pin "2") (pinfunction "K_2") (pintype "passive"))
      (node (ref "R44") (pin "7") (pinfunction "7_7") (pintype "passive"))
    )
    (net (code "89") (name "Net-(D12-K)") (class "Default")
      (node (ref "D12") (pin "2") (pinfunction "K_2") (pintype "passive"))
      (node (ref "R44") (pin "8") (pinfunction "8_8") (pintype "passive"))
    )
    (net (code "90") (name "Net-(D13-K)") (class "Default")
      (node (ref "D13") (pin "2") (pinfunction "K_2") (pintype "passive"))
      (node (ref "R44") (pin "9") (pinfunction "9_9") (pintype "passive"))
    )
    (net (code "91") (name "Net-(D14-A)") (class "Default")
      (node (ref "D14") (pin "1") (pinfunction "A_1") (pintype "passive"))
      (node (ref "MG1") (pin "2") (pinfunction "-_2") (pintype "passive"))
      (node (ref "Q9") (pin "2") (pinfunction "C_2") (pintype "passive"))
    )
    (net (code "92") (name "Net-(D15-A)") (class "Default")
      (node (ref "D15") (pin "1") (pinfunction "A_1") (pintype "passive"))
      (node (ref "R1") (pin "1") (pinfunction "1_1") (pintype "passive"))
    )
    (net (code "93") (name "Net-(D16-K)") (class "Default")
      (node (ref "D16") (pin "2") (pinfunction "K_2") (pintype "passive"))
      (node (ref "R3") (pin "2") (pinfunction "2_2") (pintype "passive"))
    )
    (net (code "94") (name "Net-(D17-K)") (class "Default")
      (node (ref "D17") (pin "2") (pinfunction "K_2") (pintype "passive"))
      (node (ref "R2") (pin "2") (pinfunction "2_2") (pintype "passive"))
    )
    (net (code "95") (name "Net-(J3-VBUS)") (class "Default")
      (node (ref "J3") (pin "1") (pinfunction "VBUS_1") (pintype "power_in"))
      (node (ref "REG1") (pin "3") (pinfunction "Vout_3") (pintype "passive"))
      (node (ref "SW5") (pin "2") (pinfunction "COMMON1_2") (pintype "passive"))
      (node (ref "SW5") (pin "5") (pinfunction "COMMON2_5") (pintype "passive"))
    )
    (net (code "96") (name "Net-(J17-Pad2)") (class "Default")
      (node (ref "J17") (pin "2") (pinfunction "2_2") (pintype "passive"))
      (node (ref "R55") (pin "1") (pinfunction "1_1") (pintype "passive"))
    )
    (net (code "97") (name "Net-(J18-Pad2)") (class "Default")
      (node (ref "J18") (pin "2") (pinfunction "2_2") (pintype "passive"))
      (node (ref "R56") (pin "1") (pinfunction "1_1") (pintype "passive"))
    )
    (net (code "98") (name "Net-(J19-Pad2)") (class "Default")
      (node (ref "J19") (pin "2") (pinfunction "2_2") (pintype "passive"))
      (node (ref "R57") (pin "1") (pinfunction "1_1") (pintype "passive"))
    )
    (net (code "99") (name "Net-(J20-Pad2)") (class "Default")
      (node (ref "J20") (pin "2") (pinfunction "2_2") (pintype "passive"))
      (node (ref "R58") (pin "1") (pinfunction "1_1") (pintype "passive"))
    )
    (net (code "100") (name "Net-(LCD1-LED+)") (class "Default")
      (node (ref "LCD1") (pin "15") (pinfunction "LED+_15") (pintype "passive"))
      (node (ref "R18") (pin "2") (pinfunction "2_2") (pintype "passive"))
    )
    (net (code "101") (name "Net-(LCD1-VCON)") (class "Default")
      (node (ref "LCD1") (pin "3") (pinfunction "VCON_3") (pintype "passive"))
      (node (ref "R52") (pin "2") (pinfunction "2_2") (pintype "passive"))
    )
    (net (code "102") (name "Net-(P1-Pad1)") (class "Default")
      (node (ref "P1") (pin "1") (pinfunction "1_1") (pintype "passive"))
      (node (ref "P1") (pin "4") (pinfunction "4_4") (pintype "passive"))
      (node (ref "P1") (pin "6") (pinfunction "6_6") (pintype "passive"))
    )
    (net (code "103") (name "Net-(Q1-G)") (class "Default")
      (node (ref "Q1") (pin "1") (pinfunction "G_1") (pintype "passive"))
      (node (ref "R31") (pin "2") (pinfunction "2_2") (pintype "passive"))
    )
    (net (code "104") (name "Net-(Q2-E)") (class "Default")
      (node (ref "Q2") (pin "2") (pinfunction "E_2") (pintype "passive"))
      (node (ref "R10") (pin "2") (pinfunction "2_2") (pintype "passive"))
      (node (ref "R11") (pin "1") (pinfunction "1_1") (pintype "passive"))
    )
    (net (code "105") (name "Net-(Q3-E)") (class "Default")
      (node (ref "Q3") (pin "2") (pinfunction "E_2") (pintype "passive"))
      (node (ref "R14") (pin "2") (pinfunction "2_2") (pintype "passive"))
      (node (ref "R15") (pin "1") (pinfunction "1_1") (pintype "passive"))
    )
    (net (code "106") (name "Net-(Q4-B)") (class "Default")
      (node (ref "Q4") (pin "1") (pinfunction "B_1") (pintype "passive"))
      (node (ref "R21") (pin "2") (pinfunction "2_2") (pintype "passive"))
    )
    (net (code "107") (name "Net-(Q5-E)") (class "Default")
      (node (ref "Q5") (pin "2") (pinfunction "E_2") (pintype "passive"))
      (node (ref "R19") (pin "2") (pinfunction "2_2") (pintype "passive"))
      (node (ref "R20") (pin "1") (pinfunction "1_1") (pintype "passive"))
    )
    (net (code "108") (name "Net-(Q6-B)") (class "Default")
      (node (ref "Q6") (pin "1") (pinfunction "B_1") (pintype "passive"))
      (node (ref "R23") (pin "1") (pinfunction "1_1") (pintype "passive"))
      (node (ref "R25") (pin "2") (pinfunction "2_2") (pintype "passive"))
    )
    (net (code "109") (name "Net-(Q7-B)") (class "Default")
      (node (ref "Q7") (pin "1") (pinfunction "B_1") (pintype "passive"))
      (node (ref "R27") (pin "1") (pinfunction "1_1") (pintype "passive"))
    )
    (net (code "110") (name "Net-(Q7-C)") (class "Default")
      (node (ref "Q7") (pin "3") (pinfunction "C_3") (pintype "passive"))
      (node (ref "R25") (pin "1") (pinfunction "1_1") (pintype "passive"))
    )
    (net (code "111") (name "Net-(Q8-B)") (class "Default")
      (node (ref "Q8") (pin "1") (pinfunction "B_1") (pintype "passive"))
      (node (ref "R29") (pin "1") (pinfunction "1_1") (pintype "passive"))
    )
    (net (code "112") (name "Net-(Q8-C)") (class "Default")
      (node (ref "Q8") (pin "3") (pinfunction "C_3") (pintype "passive"))
      (node (ref "R28") (pin "1") (pinfunction "1_1") (pintype "passive"))
    )
    (net (code "113") (name "Net-(Q9-B)") (class "Default")
      (node (ref "Q9") (pin "3") (pinfunction "B_3") (pintype "passive"))
      (node (ref "R47") (pin "2") (pinfunction "2_2") (pintype "passive"))
    )
    (net (code "114") (name "Net-(Q9-E)") (class "Default")
      (node (ref "Q9") (pin "1") (pinfunction "E_1") (pintype "passive"))
      (node (ref "R43") (pin "2") (pinfunction "2_2") (pintype "passive"))
    )
    (net (code "115") (name "Net-(R13-Pad1)") (class "Default")
      (node (ref "R13") (pin "1") (pinfunction "1_1") (pintype "passive"))
      (node (ref "U5") (pin "6") (pinfunction "D_6") (pintype "passive"))
    )
    (net (code "116") (name "Net-(R30-Pad2)") (class "Default")
      (node (ref "R30") (pin "2") (pinfunction "2_2") (pintype "passive"))
      (node (ref "U5") (pin "3") (pinfunction "G_3") (pintype "passive"))
    )
    (net (code "117") (name "Net-(R53-Pad2)") (class "Default")
      (node (ref "R53") (pin "2") (pinfunction "2_2") (pintype "passive"))
      (node (ref "R54") (pin "2") (pinfunction "2_2") (pintype "passive"))
    )
    (net (code "118") (name "Net-(U1-OSC1{slash}CLKI)") (class "Default")
      (node (ref "C7") (pin "2") (pinfunction "2_2") (pintype "passive"))
      (node (ref "U1") (pin "9") (pinfunction "OSC1/CLKI_9") (pintype "input"))
      (node (ref "Y2") (pin "1") (pinfunction "1_1") (pintype "passive"))
    )
    (net (code "119") (name "Net-(U1-OSC2{slash}CLKO{slash}RA6)") (class "Default")
      (node (ref "C8") (pin "2") (pinfunction "2_2") (pintype "passive"))
      (node (ref "U1") (pin "10") (pinfunction "OSC2/CLKO/RA6_10") (pintype "bidirectional"))
      (node (ref "Y2") (pin "2") (pinfunction "2_2") (pintype "passive"))
    )
    (net (code "120") (name "Net-(U1-VUSB)") (class "Default")
      (node (ref "C15") (pin "1") (pinfunction "1_1") (pintype "passive"))
      (node (ref "U1") (pin "14") (pinfunction "VUSB_14") (pintype "output"))
    )
    (net (code "121") (name "Net-(U2A-+)") (class "Default")
      (node (ref "R5") (pin "1") (pinfunction "1_1") (pintype "passive"))
      (node (ref "R6") (pin "2") (pinfunction "2_2") (pintype "passive"))
      (node (ref "U2") (pin "3") (pinfunction "+_3") (pintype "passive"))
    )
    (net (code "122") (name "Net-(U2A--)") (class "Default")
      (node (ref "C18") (pin "1") (pinfunction "1_1") (pintype "passive"))
      (node (ref "R4") (pin "1") (pinfunction "1_1") (pintype "passive"))
      (node (ref "U2") (pin "2") (pinfunction "-_2") (pintype "passive"))
    )
    (net (code "123") (name "Net-(U2A-OutA)") (class "Default")
      (node (ref "R31") (pin "1") (pinfunction "1_1") (pintype "passive"))
      (node (ref "U2") (pin "1") (pinfunction "OutA_1") (pintype "passive"))
    )
    (net (code "124") (name "Net-(U6-X1)") (class "Default")
      (node (ref "U6") (pin "1") (pinfunction "X1_1") (pintype "passive"))
      (node (ref "Y3") (pin "2") (pinfunction "2_2") (pintype "passive"))
    )
    (net (code "125") (name "Net-(U6-X2)") (class "Default")
      (node (ref "U6") (pin "2") (pinfunction "X2_2") (pintype "passive"))
      (node (ref "Y3") (pin "1") (pinfunction "1_1") (pintype "passive"))
    )
    (net (code "126") (name "Net-(U7-C1+)") (class "Default")
      (node (ref "C29") (pin "2") (pinfunction "2_2") (pintype "passive"))
      (node (ref "U7") (pin "1") (pinfunction "C1+_1") (pintype "passive"))
    )
    (net (code "127") (name "Net-(U7-C1-)") (class "Default")
      (node (ref "C29") (pin "1") (pinfunction "1_1") (pintype "passive"))
      (node (ref "U7") (pin "3") (pinfunction "C1-_3") (pintype "passive"))
    )
    (net (code "128") (name "Net-(U7-C2+)") (class "Default")
      (node (ref "C30") (pin "2") (pinfunction "2_2") (pintype "passive"))
      (node (ref "U7") (pin "4") (pinfunction "C2+_4") (pintype "passive"))
    )
    (net (code "129") (name "Net-(U7-C2-)") (class "Default")
      (node (ref "C30") (pin "1") (pinfunction "1_1") (pintype "passive"))
      (node (ref "U7") (pin "5") (pinfunction "C2-_5") (pintype "passive"))
    )
    (net (code "130") (name "Net-(U7-V+)") (class "Default")
      (node (ref "C31") (pin "1") (pinfunction "1_1") (pintype "passive"))
      (node (ref "U7") (pin "2") (pinfunction "V+_2") (pintype "passive"))
    )
    (net (code "131") (name "Net-(U7-V-)") (class "Default")
      (node (ref "C32") (pin "2") (pinfunction "2_2") (pintype "passive"))
      (node (ref "U7") (pin "6") (pinfunction "V-_6") (pintype "passive"))
    )
    (net (code "132") (name "VCC") (class "Default")
      (node (ref "C17") (pin "1") (pinfunction "1_1") (pintype "passive"))
      (node (ref "C19") (pin "1") (pinfunction "1_1") (pintype "passive"))
      (node (ref "C2") (pin "1") (pinfunction "1_1") (pintype "passive"))
      (node (ref "C20") (pin "1") (pinfunction "1_1") (pintype "passive"))
      (node (ref "C21") (pin "1") (pinfunction "1_1") (pintype "passive"))
      (node (ref "C23") (pin "1") (pinfunction "1_1") (pintype "passive"))
      (node (ref "C24") (pin "1") (pinfunction "1_1") (pintype "passive"))
      (node (ref "C3") (pin "1") (pinfunction "1_1") (pintype "passive"))
      (node (ref "DIP1") (pin "20") (pinfunction "VDD_20") (pintype "power_in"))
      (node (ref "DIP2") (pin "11") (pinfunction "VDD_11") (pintype "power_in"))
      (node (ref "DIP2") (pin "32") (pinfunction "VDD_32") (pintype "power_in"))
      (node (ref "J11") (pin "20") (pinfunction "20_20") (pintype "passive"))
      (node (ref "J11") (pin "40") (pinfunction "40_40") (pintype "passive"))
      (node (ref "J12") (pin "20") (pinfunction "20_20") (pintype "passive"))
      (node (ref "J12") (pin "40") (pinfunction "40_40") (pintype "passive"))
      (node (ref "J13") (pin "20") (pinfunction "20_20") (pintype "passive"))
      (node (ref "J13") (pin "40") (pinfunction "40_40") (pintype "passive"))
      (node (ref "J14") (pin "4") (pinfunction "4_4") (pintype "passive"))
      (node (ref "J17") (pin "1") (pinfunction "1_1") (pintype "passive"))
      (node (ref "J18") (pin "1") (pinfunction "1_1") (pintype "passive"))
      (node (ref "J19") (pin "1") (pinfunction "1_1") (pintype "passive"))
      (node (ref "J2") (pin "1") (pinfunction "VBUS_1") (pintype "power_in"))
      (node (ref "J20") (pin "1") (pinfunction "1_1") (pintype "passive"))
      (node (ref "J21") (pin "2") (pinfunction "2_2") (pintype "passive"))
      (node (ref "J4") (pin "10") (pinfunction "10_10") (pintype "passive"))
      (node (ref "J5") (pin "10") (pinfunction "10_10") (pintype "passive"))
      (node (ref "J6") (pin "10") (pinfunction "10_10") (pintype "passive"))
      (node (ref "J7") (pin "10") (pinfunction "10_10") (pintype "passive"))
      (node (ref "J8") (pin "10") (pinfunction "10_10") (pintype "passive"))
      (node (ref "Q1") (pin "2") (pinfunction "S_2") (pintype "passive"))
      (node (ref "R1") (pin "2") (pinfunction "2_2") (pintype "passive"))
      (node (ref "R16") (pin "1") (pinfunction "1_1") (pintype "passive"))
      (node (ref "R2") (pin "1") (pinfunction "1_1") (pintype "passive"))
      (node (ref "R32") (pin "2") (pinfunction "2_2") (pintype "passive"))
      (node (ref "R34") (pin "2") (pinfunction "2_2") (pintype "passive"))
      (node (ref "R48") (pin "2") (pinfunction "2_2") (pintype "passive"))
      (node (ref "R49") (pin "2") (pinfunction "2_2") (pintype "passive"))
      (node (ref "R51") (pin "2") (pinfunction "2_2") (pintype "passive"))
      (node (ref "R54") (pin "3") (pinfunction "3_3") (pintype "passive"))
      (node (ref "R8") (pin "2") (pinfunction "2_2") (pintype "passive"))
      (node (ref "R9") (pin "2") (pinfunction "2_2") (pintype "passive"))
      (node (ref "SW2") (pin "3") (pinfunction "3_3") (pintype "passive"))
      (node (ref "SW3") (pin "5") (pinfunction "5_5") (pintype "passive"))
      (node (ref "SW3") (pin "6") (pinfunction "6_6") (pintype "passive"))
      (node (ref "SW3") (pin "7") (pinfunction "7_7") (pintype "passive"))
      (node (ref "SW4") (pin "1") (pinfunction "1_1") (pintype "passive"))
      (node (ref "SW5") (pin "3") (pinfunction "NO1_3") (pintype "passive"))
      (node (ref "SW5") (pin "6") (pinfunction "NO2_6") (pintype "passive"))
      (node (ref "U1") (pin "20") (pinfunction "VDD_20") (pintype "power_in"))
      (node (ref "U2") (pin "8") (pinfunction "VCC_8") (pintype "passive"))
      (node (ref "U6") (pin "8") (pinfunction "VCC_8") (pintype "passive"))
    )
    (net (code "133") (name "unconnected-(J1-S-Pad3)") (class "Default")
      (node (ref "J1") (pin "3") (pinfunction "S_3") (pintype "power_in+no_connect"))
    )
    (net (code "134") (name "unconnected-(J2-SHLD-Pad5)") (class "Default")
      (node (ref "J2") (pin "5") (pinfunction "SHLD_5") (pintype "passive+no_connect"))
    )
    (net (code "135") (name "unconnected-(J2-SHLD-Pad6)") (class "Default")
      (node (ref "J2") (pin "6") (pinfunction "SHLD_6") (pintype "passive+no_connect"))
    )
    (net (code "136") (name "unconnected-(J3-SHLD-Pad5)") (class "Default")
      (node (ref "J3") (pin "5") (pinfunction "SHLD_5") (pintype "passive+no_connect"))
    )
    (net (code "137") (name "unconnected-(J3-SHLD-Pad6)") (class "Default")
      (node (ref "J3") (pin "6") (pinfunction "SHLD_6") (pintype "passive+no_connect"))
    )
    (net (code "138") (name "unconnected-(J8-Pad5)") (class "Default")
      (node (ref "J8") (pin "5") (pinfunction "5_5") (pintype "passive+no_connect"))
    )
    (net (code "139") (name "unconnected-(J8-Pad6)") (class "Default")
      (node (ref "J8") (pin "6") (pinfunction "6_6") (pintype "passive+no_connect"))
    )
    (net (code "140") (name "unconnected-(J8-Pad7)") (class "Default")
      (node (ref "J8") (pin "7") (pinfunction "7_7") (pintype "passive+no_connect"))
    )
    (net (code "141") (name "unconnected-(J8-Pad8)") (class "Default")
      (node (ref "J8") (pin "8") (pinfunction "8_8") (pintype "passive+no_connect"))
    )
    (net (code "142") (name "unconnected-(J14-Pad2)") (class "Default")
      (node (ref "J14") (pin "2") (pinfunction "2_2") (pintype "passive+no_connect"))
    )
    (net (code "143") (name "unconnected-(J14-Pad6)") (class "Default")
      (node (ref "J14") (pin "6") (pinfunction "6_6") (pintype "passive+no_connect"))
    )
    (net (code "144") (name "unconnected-(J14-PadS)") (class "Default")
      (node (ref "J14") (pin "S") (pinfunction "S_S") (pintype "input+no_connect"))
    )
    (net (code "145") (name "unconnected-(J17-Pad3)") (class "Default")
      (node (ref "J17") (pin "3") (pinfunction "3_3") (pintype "passive+no_connect"))
    )
    (net (code "146") (name "unconnected-(J18-Pad3)") (class "Default")
      (node (ref "J18") (pin "3") (pinfunction "3_3") (pintype "passive+no_connect"))
    )
    (net (code "147") (name "unconnected-(J19-Pad3)") (class "Default")
      (node (ref "J19") (pin "3") (pinfunction "3_3") (pintype "passive+no_connect"))
    )
    (net (code "148") (name "unconnected-(J20-Pad3)") (class "Default")
      (node (ref "J20") (pin "3") (pinfunction "3_3") (pintype "passive+no_connect"))
    )
    (net (code "149") (name "unconnected-(J21-Pad6)") (class "Default")
      (node (ref "J21") (pin "6") (pinfunction "6_6") (pintype "passive+no_connect"))
    )
    (net (code "150") (name "unconnected-(LCD1-D0-Pad7)") (class "Default")
      (node (ref "LCD1") (pin "7") (pinfunction "D0_7") (pintype "passive+no_connect"))
    )
    (net (code "151") (name "unconnected-(LCD1-D1-Pad8)") (class "Default")
      (node (ref "LCD1") (pin "8") (pinfunction "D1_8") (pintype "passive+no_connect"))
    )
    (net (code "152") (name "unconnected-(LCD1-D2-Pad9)") (class "Default")
      (node (ref "LCD1") (pin "9") (pinfunction "D2_9") (pintype "passive+no_connect"))
    )
    (net (code "153") (name "unconnected-(LCD1-D3-Pad10)") (class "Default")
      (node (ref "LCD1") (pin "10") (pinfunction "D3_10") (pintype "passive+no_connect"))
    )
    (net (code "154") (name "unconnected-(P1-Pad7)") (class "Default")
      (node (ref "P1") (pin "7") (pinfunction "7_7") (pintype "passive+no_connect"))
    )
    (net (code "155") (name "unconnected-(P1-Pad8)") (class "Default")
      (node (ref "P1") (pin "8") (pinfunction "8_8") (pintype "passive+no_connect"))
    )
    (net (code "156") (name "unconnected-(P1-Pad9)") (class "Default")
      (node (ref "P1") (pin "9") (pinfunction "9_9") (pintype "passive+no_connect"))
    )
    (net (code "157") (name "unconnected-(SW5-NC1-Pad1)") (class "Default")
      (node (ref "SW5") (pin "1") (pinfunction "NC1_1") (pintype "passive+no_connect"))
    )
    (net (code "158") (name "unconnected-(SW5-NC2-Pad4)") (class "Default")
      (node (ref "SW5") (pin "4") (pinfunction "NC2_4") (pintype "passive+no_connect"))
    )
    (net (code "159") (name "unconnected-(U1-RB6{slash}KBI2{slash}PGC-Pad27)") (class "Default")
      (node (ref "U1") (pin "27") (pinfunction "RB6/KBI2/PGC_27") (pintype "bidirectional+no_connect"))
    )
    (net (code "160") (name "unconnected-(U1-RB7{slash}KBI3{slash}PGD-Pad28)") (class "Default")
      (node (ref "U1") (pin "28") (pinfunction "RB7/KBI3/PGD_28") (pintype "bidirectional+no_connect"))
    )
    (net (code "161") (name "unconnected-(U1-RC6{slash}TX{slash}CK-Pad17)") (class "Default")
      (node (ref "U1") (pin "17") (pinfunction "RC6/TX/CK_17") (pintype "bidirectional+no_connect"))
    )
    (net (code "162") (name "unconnected-(U1-RC7{slash}RX{slash}DT{slash}SDO-Pad18)") (class "Default")
      (node (ref "U1") (pin "18") (pinfunction "RC7/RX/DT/SDO_18") (pintype "bidirectional+no_connect"))
    )
    (net (code "163") (name "unconnected-(U1-~{MCLR}{slash}VPP{slash}RE3-Pad1)") (class "Default")
      (node (ref "U1") (pin "1") (pinfunction "~{MCLR}/VPP/RE3_1") (pintype "input+no_connect"))
    )
    (net (code "164") (name "unconnected-(U6-OUT-Pad7)") (class "Default")
      (node (ref "U6") (pin "7") (pinfunction "OUT_7") (pintype "passive+no_connect"))
    )
    (net (code "165") (name "unconnected-(U7-DIN2-Pad10)") (class "Default")
      (node (ref "U7") (pin "10") (pinfunction "DIN2_10") (pintype "passive+no_connect"))
    )
    (net (code "166") (name "unconnected-(U7-DOUT2-Pad7)") (class "Default")
      (node (ref "U7") (pin "7") (pinfunction "DOUT2_7") (pintype "passive+no_connect"))
    )
    (net (code "167") (name "unconnected-(U7-RIN2-Pad8)") (class "Default")
      (node (ref "U7") (pin "8") (pinfunction "RIN2_8") (pintype "passive+no_connect"))
    )
    (net (code "168") (name "unconnected-(U7-ROUT2-Pad9)") (class "Default")
      (node (ref "U7") (pin "9") (pinfunction "ROUT2_9") (pintype "passive+no_connect"))
    )
  )
)
